# HDMI_RGB_LVDS_fertig_V3_nacked_keine_sti.net
KiCad netlist of a schematic drawn in EAGLE
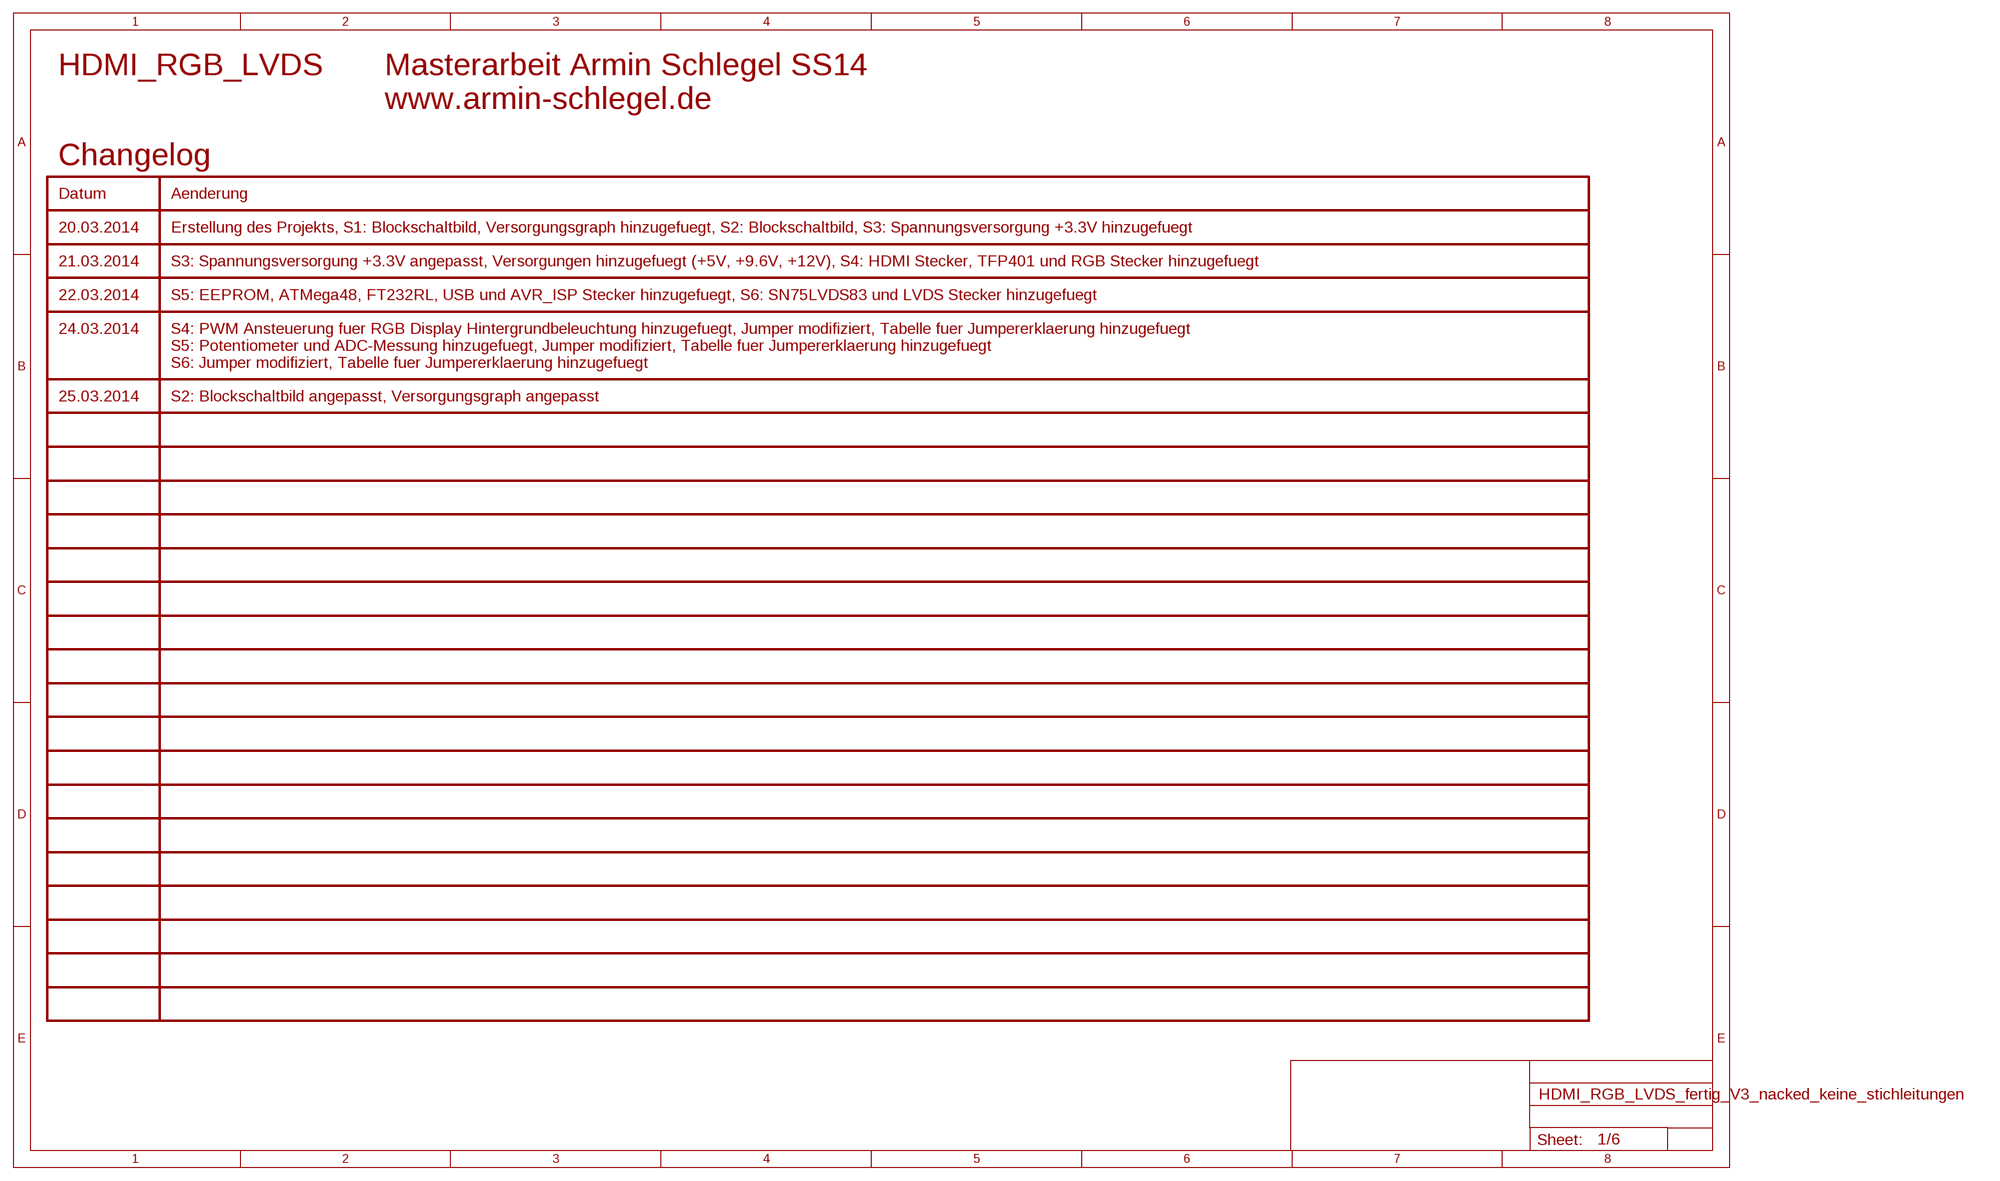
[diagram p0: schematic, sheet 1]
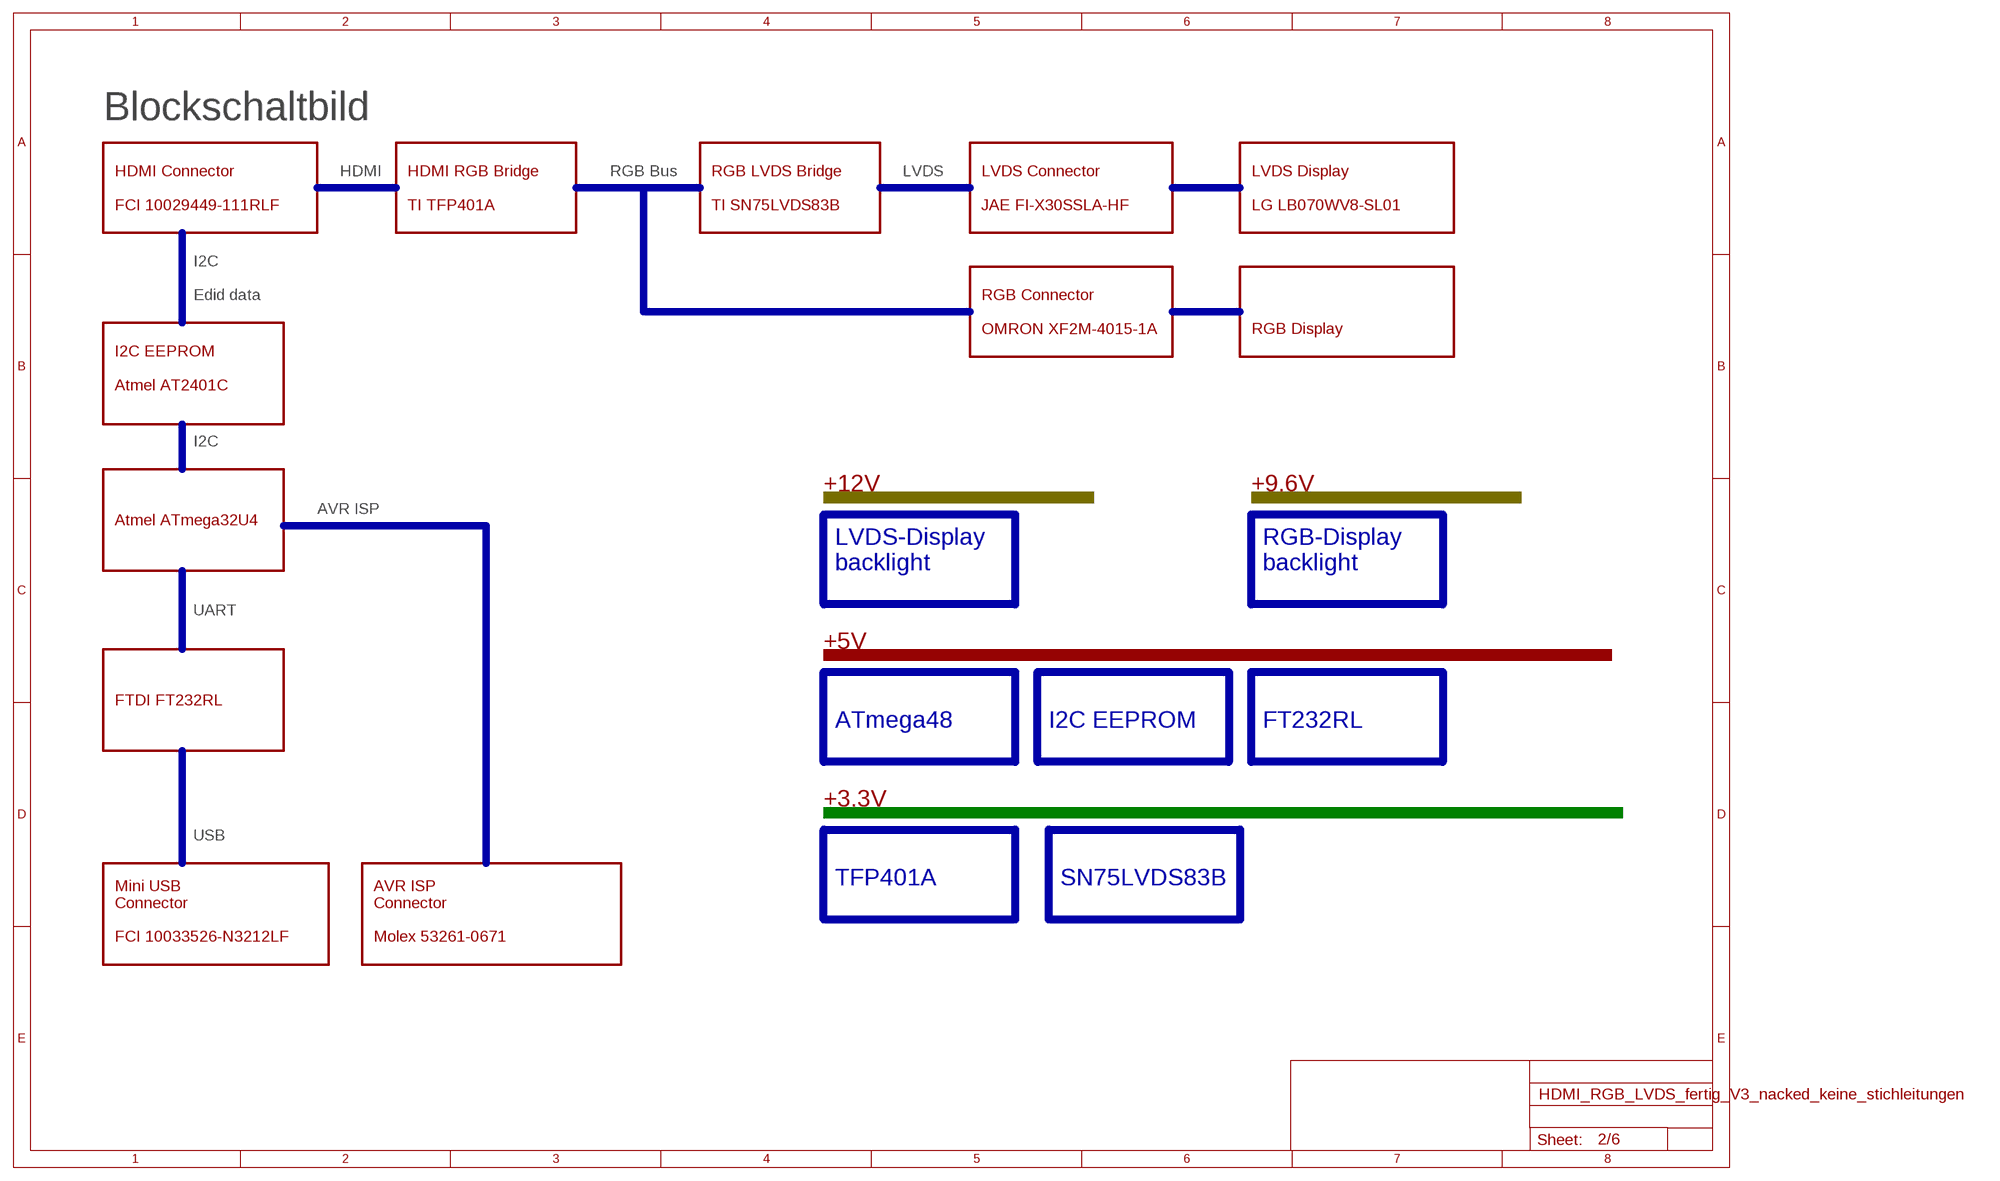
[diagram p1: schematic, sheet 2]
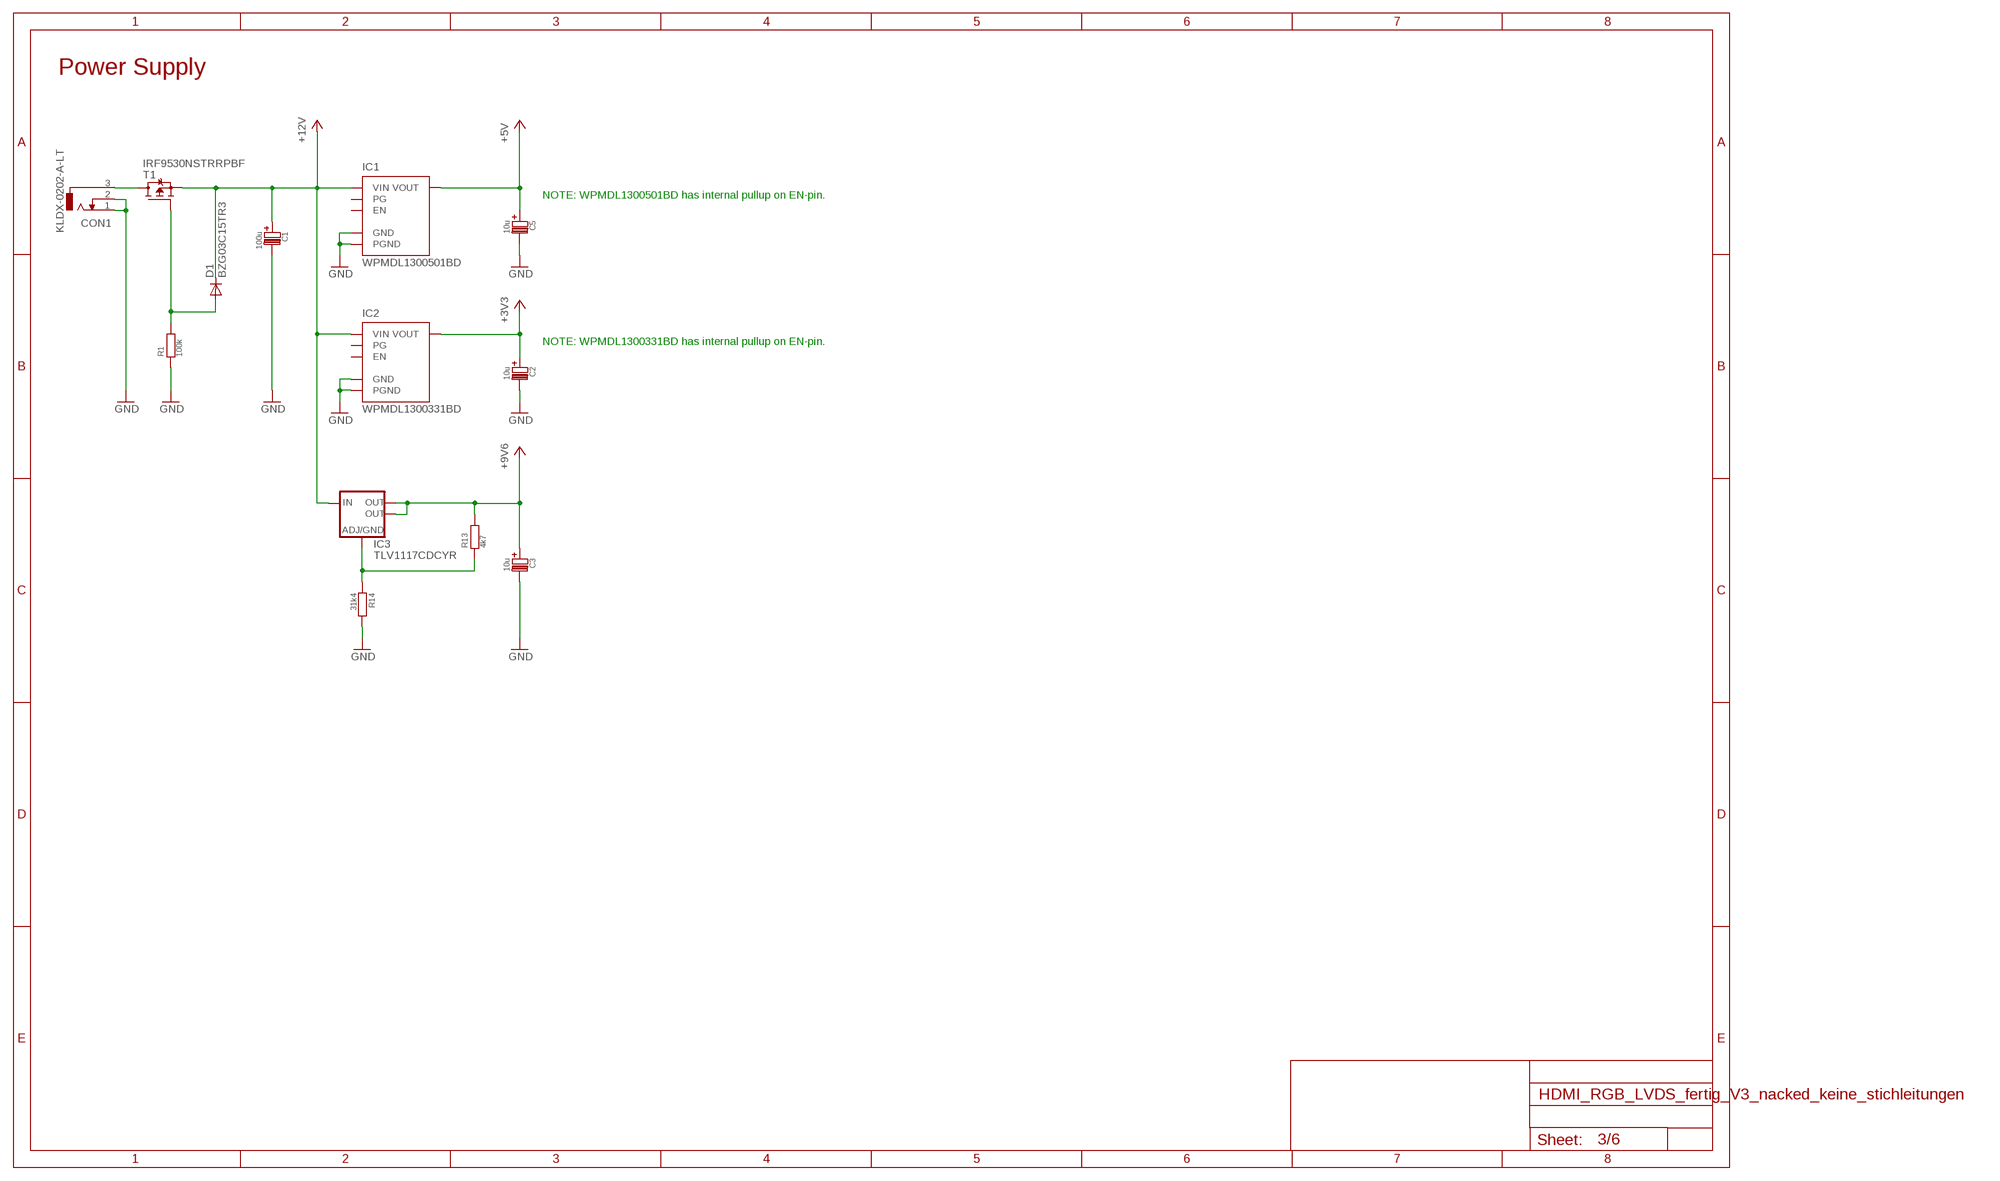
[diagram p2: schematic, sheet 3]
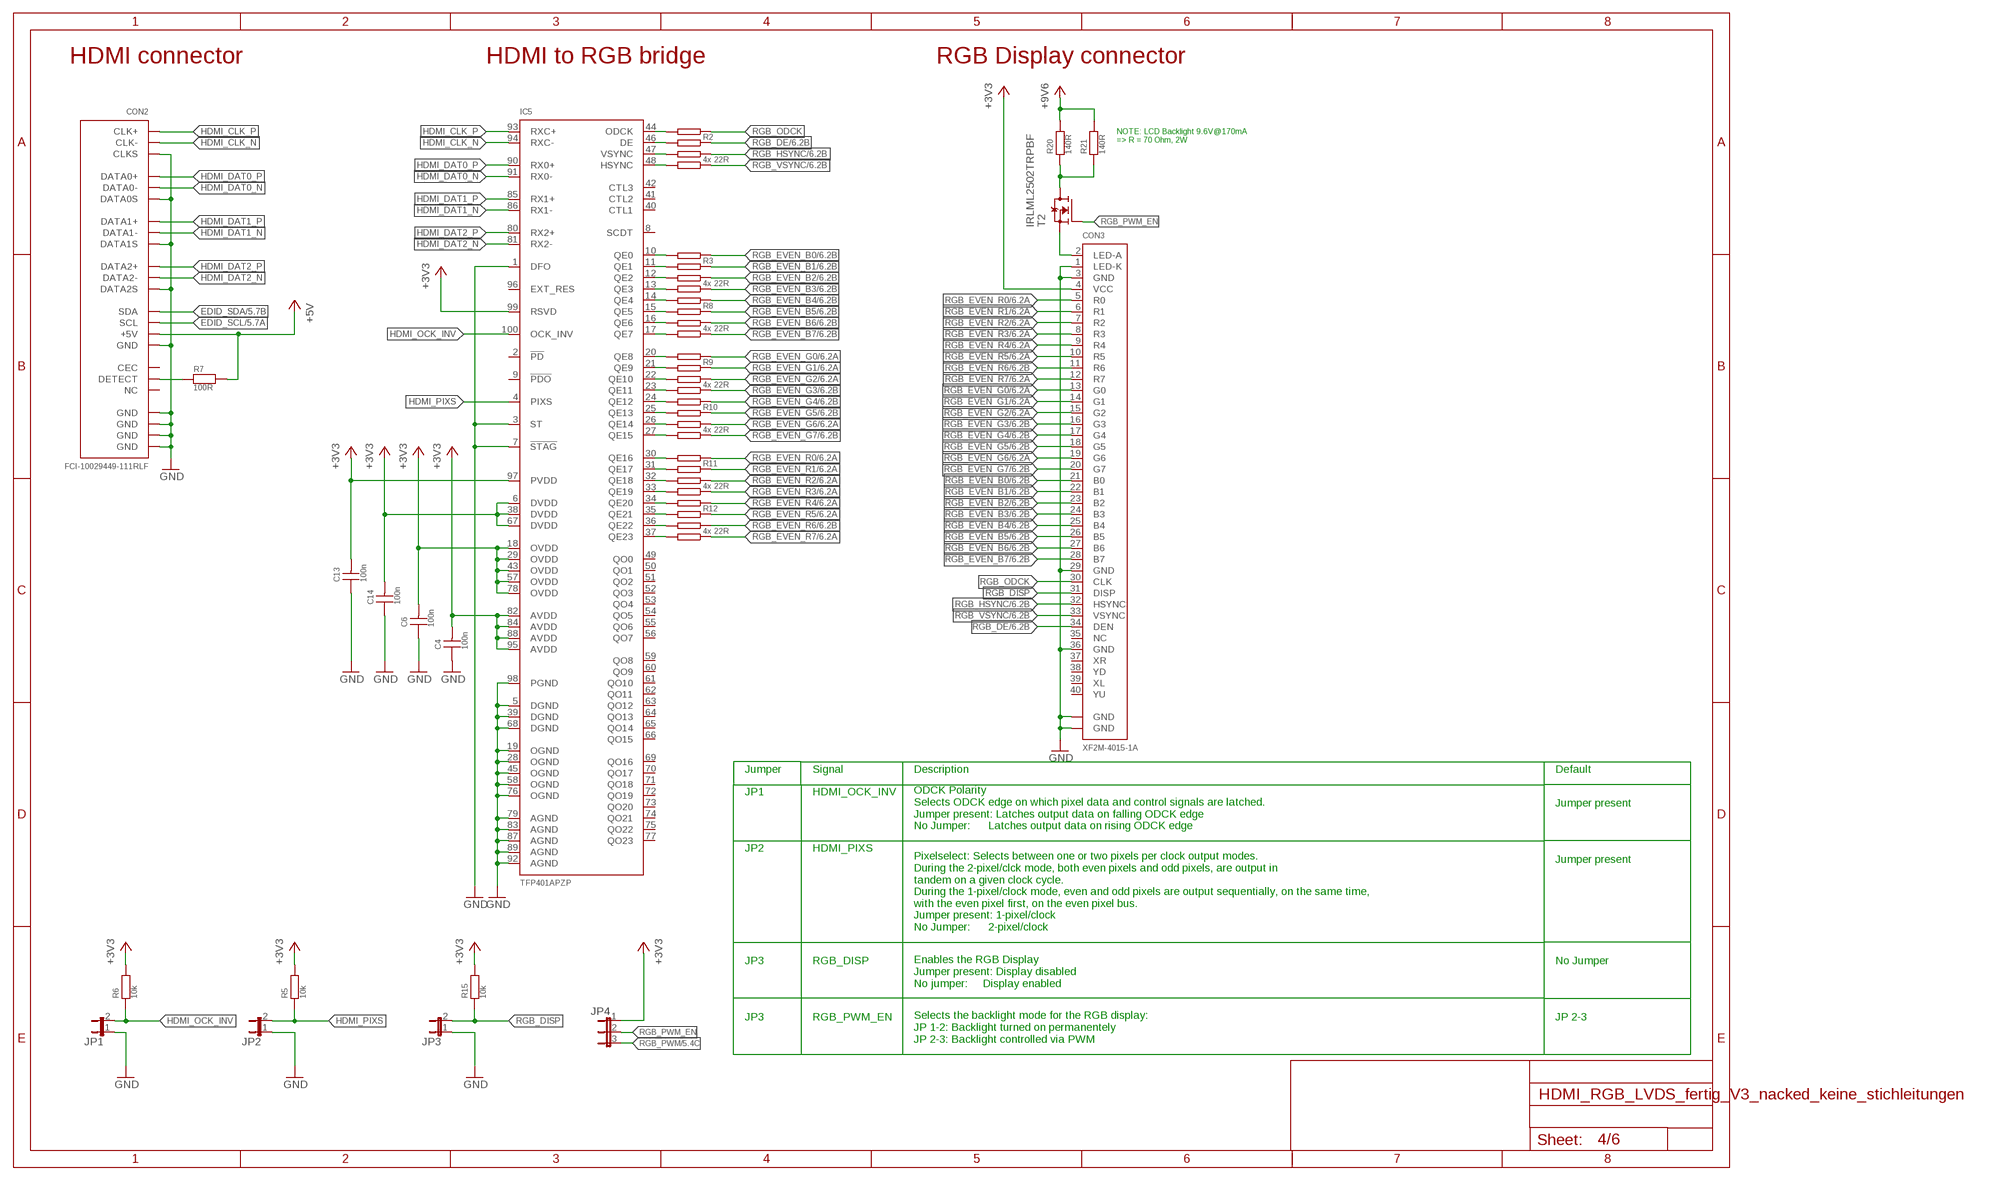
[diagram p3: schematic, sheet 4]
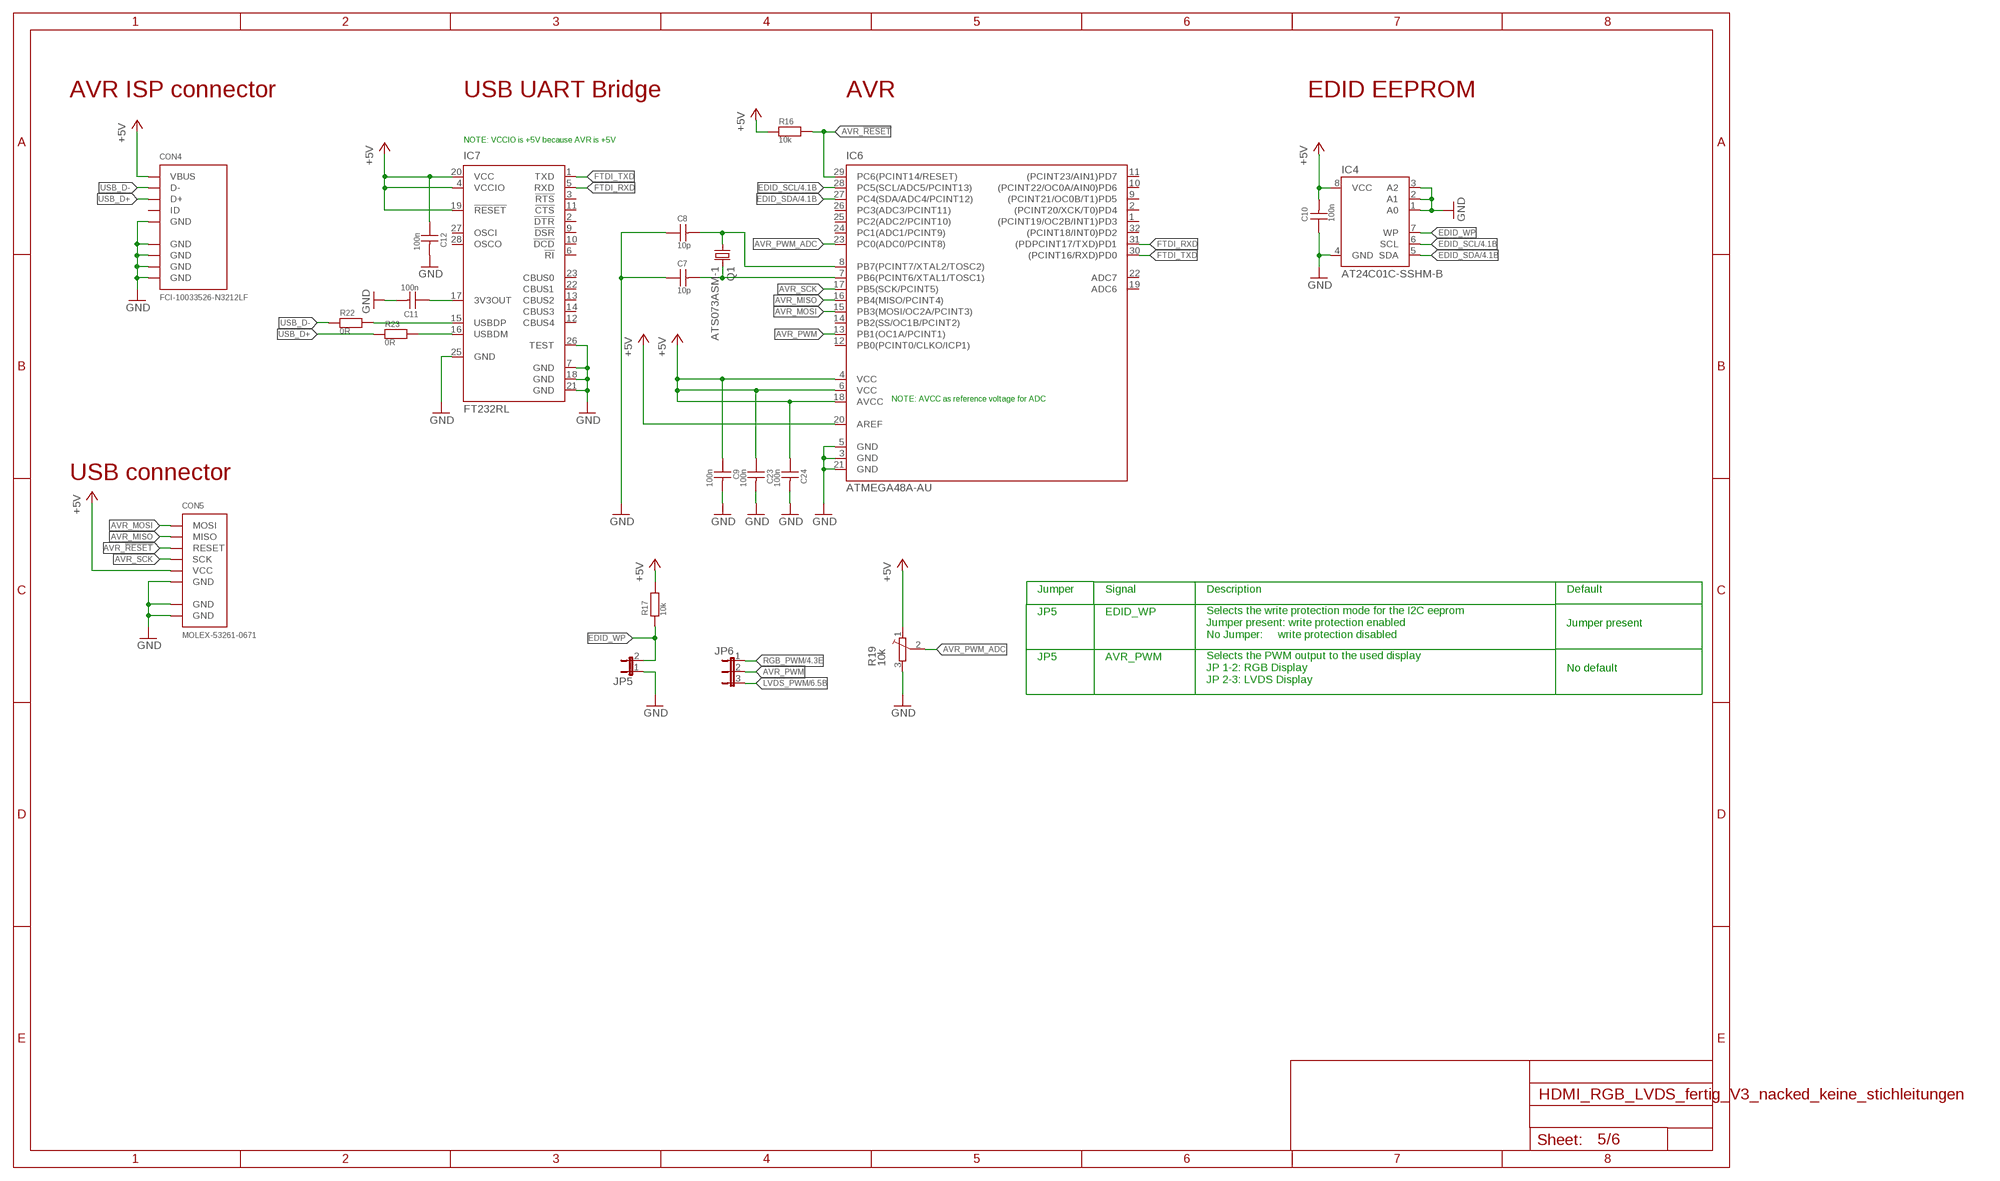
[diagram p4: schematic, sheet 5]
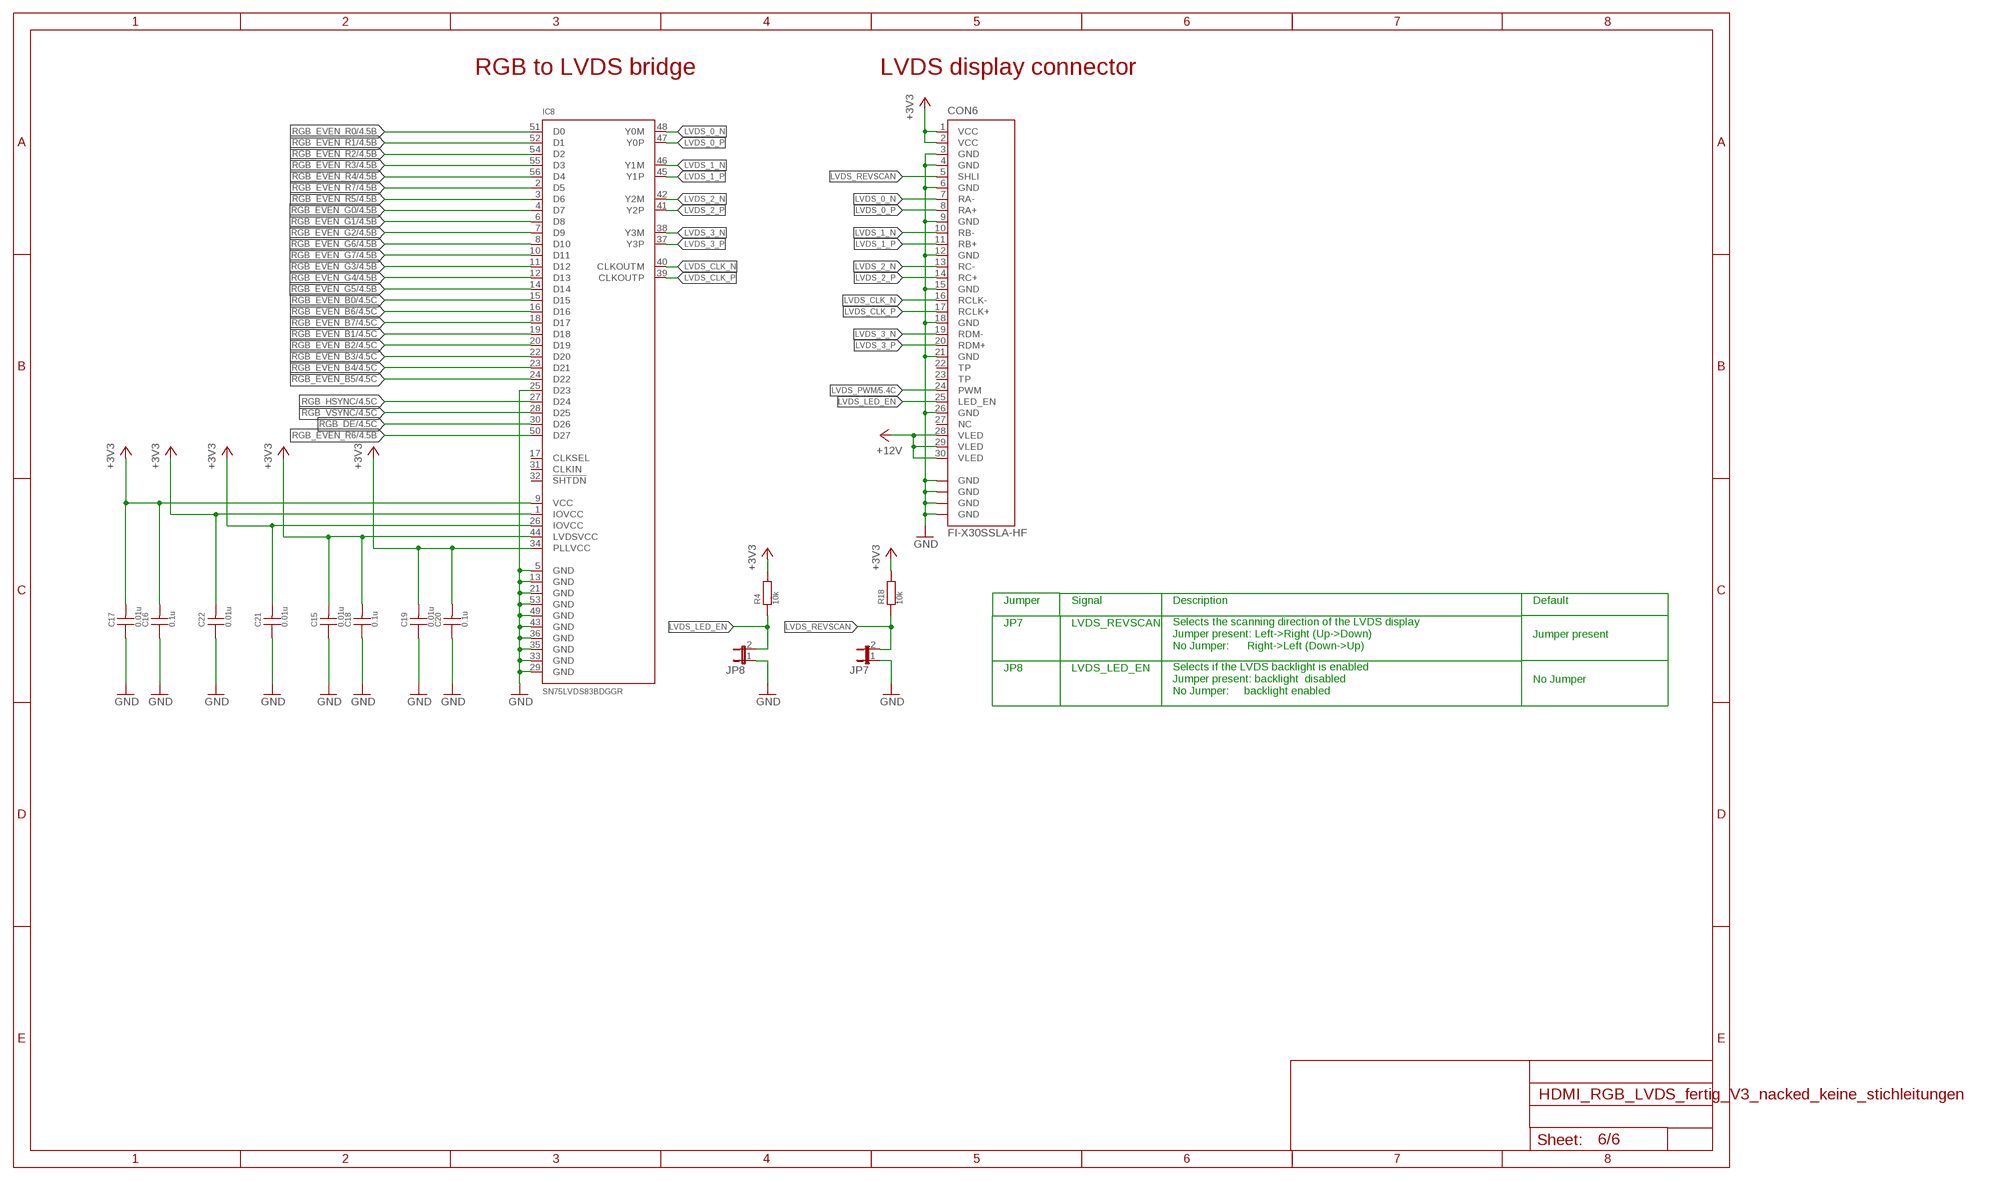
[diagram p5: schematic, sheet 6]

(export (version "E")
  (design (tool "Eeschema 10.0.6"))
  (components
    (comp (ref "C1")
      (value "100u")
      (footprint "eagle-import:C_POL_6X6MM")
      (libsource (lib "eagle-import") (part "C_POL6X6MM"))
    )
    (comp (ref "C2")
      (value "10u")
      (footprint "eagle-import:C_POL_4X4MM")
      (libsource (lib "eagle-import") (part "C_POL4X4MM"))
    )
    (comp (ref "C3")
      (value "10u")
      (footprint "eagle-import:C_POL_4X4MM")
      (libsource (lib "eagle-import") (part "C_POL4X4MM"))
    )
    (comp (ref "C5")
      (value "10u")
      (footprint "eagle-import:C_POL_4X4MM")
      (libsource (lib "eagle-import") (part "C_POL4X4MM"))
    )
    (comp (ref "CON1")
      (value "KLDX-0202-A-LT")
      (footprint "eagle-import:KLDX-0202-A-LT")
      (libsource (lib "eagle-import") (part "KLDX-0202-A-LT"))
    )
    (comp (ref "D1")
      (value "BZG03C15TR3")
      (footprint "eagle-import:DO214A")
      (libsource (lib "eagle-import") (part "BZG03C15TR3"))
    )
    (comp (ref "IC1")
      (value "WPMDL1300501BD")
      (footprint "eagle-import:TO263-5")
      (libsource (lib "eagle-import") (part "WPMDL1300501BD"))
    )
    (comp (ref "IC2")
      (value "WPMDL1300331BD")
      (footprint "eagle-import:TO263-5")
      (libsource (lib "eagle-import") (part "WPMDL1300331BD"))
    )
    (comp (ref "IC3")
      (value "TLV1117CDCYR")
      (footprint "eagle-import:SOT223")
      (libsource (lib "eagle-import") (part "TLV1117CDCYR"))
    )
    (comp (ref "R1")
      (value "100k")
      (footprint "eagle-import:R0402")
      (libsource (lib "eagle-import") (part "R0402"))
    )
    (comp (ref "R13")
      (value "4k7")
      (footprint "eagle-import:R0402")
      (libsource (lib "eagle-import") (part "R0402"))
    )
    (comp (ref "R14")
      (value "31k4")
      (footprint "eagle-import:R0402")
      (libsource (lib "eagle-import") (part "R0402"))
    )
    (comp (ref "T1")
      (value "IRF9530NSTRRPBF")
      (footprint "eagle-import:D2PAK")
      (libsource (lib "eagle-import") (part "IRF9530NSTRRPBF"))
    )
    (comp (ref "U$2")
      (value "FRAME_A3_LANDSCAPE")
      (footprint "eagle-import:FRAME")
      (libsource (lib "eagle-import") (part "FRAME_A3_LANDSCAPE"))
    )
    (comp (ref "U$1")
      (value "FRAME_A3_LANDSCAPE")
      (footprint "eagle-import:FRAME")
      (libsource (lib "eagle-import") (part "FRAME_A3_LANDSCAPE"))
    )
    (comp (ref "C4")
      (value "100n")
      (footprint "eagle-import:C0402")
      (libsource (lib "eagle-import") (part "C_SMD0402"))
    )
    (comp (ref "C6")
      (value "100n")
      (footprint "eagle-import:C0402")
      (libsource (lib "eagle-import") (part "C_SMD0402"))
    )
    (comp (ref "C13")
      (value "100n")
      (footprint "eagle-import:C0402")
      (libsource (lib "eagle-import") (part "C_SMD0402"))
    )
    (comp (ref "C14")
      (value "100n")
      (footprint "eagle-import:C0402")
      (libsource (lib "eagle-import") (part "C_SMD0402"))
    )
    (comp (ref "CON2")
      (value "FCI-10029449-111RLF")
      (footprint "eagle-import:FCI-10029449-111RLF")
      (libsource (lib "eagle-import") (part "FCI-10029449-111RLF"))
    )
    (comp (ref "CON3")
      (value "XF2M-4015-1A")
      (footprint "eagle-import:XF2M-4015-1A")
      (libsource (lib "eagle-import") (part "XF2M-4015-1A"))
    )
    (comp (ref "IC5")
      (value "TFP401APZP")
      (footprint "eagle-import:HTQFP-100")
      (libsource (lib "eagle-import") (part "TFP401APZP"))
    )
    (comp (ref "JP1")
      (value "JUMPER2")
      (footprint "eagle-import:JUMPER2_THROUGHHOLE")
      (libsource (lib "eagle-import") (part "JUMPER2"))
    )
    (comp (ref "JP2")
      (value "JUMPER2")
      (footprint "eagle-import:JUMPER2_THROUGHHOLE")
      (libsource (lib "eagle-import") (part "JUMPER2"))
    )
    (comp (ref "JP3")
      (value "JUMPER2")
      (footprint "eagle-import:JUMPER2_THROUGHHOLE")
      (libsource (lib "eagle-import") (part "JUMPER2"))
    )
    (comp (ref "JP4")
      (value "JUMPER3")
      (footprint "eagle-import:JUMPER3_THROUGHHOLE")
      (libsource (lib "eagle-import") (part "JUMPER3"))
    )
    (comp (ref "R2")
      (value "22R")
      (footprint "eagle-import:R-ARRAY-4X0603")
      (libsource (lib "eagle-import") (part "CTR-742C083220JP-4X22R-4X0603"))
    )
    (comp (ref "R3")
      (value "22R")
      (footprint "eagle-import:R-ARRAY-4X0603")
      (libsource (lib "eagle-import") (part "CTR-742C083220JP-4X22R-4X0603"))
    )
    (comp (ref "R5")
      (value "10k")
      (footprint "eagle-import:R0402")
      (libsource (lib "eagle-import") (part "R0402"))
    )
    (comp (ref "R6")
      (value "10k")
      (footprint "eagle-import:R0402")
      (libsource (lib "eagle-import") (part "R0402"))
    )
    (comp (ref "R7")
      (value "100R")
      (footprint "eagle-import:R0402")
      (libsource (lib "eagle-import") (part "R0402"))
    )
    (comp (ref "R8")
      (value "22R")
      (footprint "eagle-import:R-ARRAY-4X0603")
      (libsource (lib "eagle-import") (part "CTR-742C083220JP-4X22R-4X0603"))
    )
    (comp (ref "R9")
      (value "22R")
      (footprint "eagle-import:R-ARRAY-4X0603")
      (libsource (lib "eagle-import") (part "CTR-742C083220JP-4X22R-4X0603"))
    )
    (comp (ref "R10")
      (value "22R")
      (footprint "eagle-import:R-ARRAY-4X0603")
      (libsource (lib "eagle-import") (part "CTR-742C083220JP-4X22R-4X0603"))
    )
    (comp (ref "R11")
      (value "22R")
      (footprint "eagle-import:R-ARRAY-4X0603")
      (libsource (lib "eagle-import") (part "CTR-742C083220JP-4X22R-4X0603"))
    )
    (comp (ref "R12")
      (value "22R")
      (footprint "eagle-import:R-ARRAY-4X0603")
      (libsource (lib "eagle-import") (part "CTR-742C083220JP-4X22R-4X0603"))
    )
    (comp (ref "R15")
      (value "10k")
      (footprint "eagle-import:R0402")
      (libsource (lib "eagle-import") (part "R0402"))
    )
    (comp (ref "R20")
      (value "140R")
      (footprint "eagle-import:R2512")
      (libsource (lib "eagle-import") (part "R2512"))
    )
    (comp (ref "R21")
      (value "140R")
      (footprint "eagle-import:R2512")
      (libsource (lib "eagle-import") (part "R2512"))
    )
    (comp (ref "T2")
      (value "IRLML2502TRPBF")
      (footprint "eagle-import:SOT23")
      (libsource (lib "eagle-import") (part "IRLML2502TRPBF"))
    )
    (comp (ref "U$3")
      (value "FRAME_A3_LANDSCAPE")
      (footprint "eagle-import:FRAME")
      (libsource (lib "eagle-import") (part "FRAME_A3_LANDSCAPE"))
    )
    (comp (ref "C7")
      (value "10p")
      (footprint "eagle-import:C0402")
      (libsource (lib "eagle-import") (part "C_SMD0402"))
    )
    (comp (ref "C8")
      (value "10p")
      (footprint "eagle-import:C0402")
      (libsource (lib "eagle-import") (part "C_SMD0402"))
    )
    (comp (ref "C9")
      (value "100n")
      (footprint "eagle-import:C0402")
      (libsource (lib "eagle-import") (part "C_SMD0402"))
    )
    (comp (ref "C10")
      (value "100n")
      (footprint "eagle-import:C0402")
      (libsource (lib "eagle-import") (part "C_SMD0402"))
    )
    (comp (ref "C11")
      (value "100n")
      (footprint "eagle-import:C0402")
      (libsource (lib "eagle-import") (part "C_SMD0402"))
    )
    (comp (ref "C12")
      (value "100n")
      (footprint "eagle-import:C0402")
      (libsource (lib "eagle-import") (part "C_SMD0402"))
    )
    (comp (ref "C23")
      (value "100n")
      (footprint "eagle-import:C0402")
      (libsource (lib "eagle-import") (part "C_SMD0402"))
    )
    (comp (ref "C24")
      (value "100n")
      (footprint "eagle-import:C0402")
      (libsource (lib "eagle-import") (part "C_SMD0402"))
    )
    (comp (ref "CON4")
      (value "FCI-10033526-N3212LF")
      (footprint "eagle-import:FCI-10033526-N3212LF")
      (libsource (lib "eagle-import") (part "FCI-10033526-N3212LF"))
    )
    (comp (ref "CON5")
      (value "MOLEX-53261-0671")
      (footprint "eagle-import:MOLEX-53261-0671")
      (libsource (lib "eagle-import") (part "MOLEX-53261-0671"))
    )
    (comp (ref "IC4")
      (value "AT24C01C-SSHM-B")
      (footprint "eagle-import:SOIC8")
      (libsource (lib "eagle-import") (part "AT24C01C-SSHM-B"))
    )
    (comp (ref "IC6")
      (value "ATMEGA48A-AU")
      (footprint "eagle-import:TQFP32")
      (libsource (lib "eagle-import") (part "ATMEGA48A-AU"))
    )
    (comp (ref "IC7")
      (value "FT232RL")
      (footprint "eagle-import:SSOP28")
      (libsource (lib "eagle-import") (part "FT232RL"))
    )
    (comp (ref "JP5")
      (value "JUMPER2")
      (footprint "eagle-import:JUMPER2_THROUGHHOLE")
      (libsource (lib "eagle-import") (part "JUMPER2"))
    )
    (comp (ref "JP6")
      (value "JUMPER3")
      (footprint "eagle-import:JUMPER3_THROUGHHOLE")
      (libsource (lib "eagle-import") (part "JUMPER3"))
    )
    (comp (ref "Q1")
      (value "ATS073ASM-1")
      (footprint "eagle-import:HC49_USSM")
      (libsource (lib "eagle-import") (part "ATS073ASM-1"))
    )
    (comp (ref "R16")
      (value "10k")
      (footprint "eagle-import:R0402")
      (libsource (lib "eagle-import") (part "R0402"))
    )
    (comp (ref "R17")
      (value "10k")
      (footprint "eagle-import:R0402")
      (libsource (lib "eagle-import") (part "R0402"))
    )
    (comp (ref "R19")
      (value "10k")
      (footprint "eagle-import:35WR5KLFTR")
      (libsource (lib "eagle-import") (part "35WR5KLFTR"))
    )
    (comp (ref "R22")
      (value "0R")
      (footprint "eagle-import:R0402")
      (libsource (lib "eagle-import") (part "R0402"))
    )
    (comp (ref "R23")
      (value "0R")
      (footprint "eagle-import:R0402")
      (libsource (lib "eagle-import") (part "R0402"))
    )
    (comp (ref "U$4")
      (value "FRAME_A3_LANDSCAPE")
      (footprint "eagle-import:FRAME")
      (libsource (lib "eagle-import") (part "FRAME_A3_LANDSCAPE"))
    )
    (comp (ref "C15")
      (value "0.01u")
      (footprint "eagle-import:C0402")
      (libsource (lib "eagle-import") (part "C_SMD0402"))
    )
    (comp (ref "C16")
      (value "0.1u")
      (footprint "eagle-import:C0402")
      (libsource (lib "eagle-import") (part "C_SMD0402"))
    )
    (comp (ref "C17")
      (value "0.01u")
      (footprint "eagle-import:C0402")
      (libsource (lib "eagle-import") (part "C_SMD0402"))
    )
    (comp (ref "C18")
      (value "0.1u")
      (footprint "eagle-import:C0402")
      (libsource (lib "eagle-import") (part "C_SMD0402"))
    )
    (comp (ref "C19")
      (value "0.01u")
      (footprint "eagle-import:C0402")
      (libsource (lib "eagle-import") (part "C_SMD0402"))
    )
    (comp (ref "C20")
      (value "0.1u")
      (footprint "eagle-import:C0402")
      (libsource (lib "eagle-import") (part "C_SMD0402"))
    )
    (comp (ref "C21")
      (value "0.01u")
      (footprint "eagle-import:C0402")
      (libsource (lib "eagle-import") (part "C_SMD0402"))
    )
    (comp (ref "C22")
      (value "0.01u")
      (footprint "eagle-import:C0402")
      (libsource (lib "eagle-import") (part "C_SMD0402"))
    )
    (comp (ref "CON6")
      (value "FI-X30SSLA-HF")
      (footprint "eagle-import:FI-X30SSLA-HF")
      (libsource (lib "eagle-import") (part "FI-X30SSLA-HF"))
    )
    (comp (ref "IC8")
      (value "SN75LVDS83BDGGR")
      (footprint "eagle-import:TSSOP-56")
      (libsource (lib "eagle-import") (part "SN75LVDS83BDGGR"))
    )
    (comp (ref "JP7")
      (value "JUMPER2")
      (footprint "eagle-import:JUMPER2_THROUGHHOLE")
      (libsource (lib "eagle-import") (part "JUMPER2"))
    )
    (comp (ref "JP8")
      (value "JUMPER2")
      (footprint "eagle-import:JUMPER2_THROUGHHOLE")
      (libsource (lib "eagle-import") (part "JUMPER2"))
    )
    (comp (ref "R4")
      (value "10k")
      (footprint "eagle-import:R0402")
      (libsource (lib "eagle-import") (part "R0402"))
    )
    (comp (ref "R18")
      (value "10k")
      (footprint "eagle-import:R0402")
      (libsource (lib "eagle-import") (part "R0402"))
    )
    (comp (ref "U$5")
      (value "FRAME_A3_LANDSCAPE")
      (footprint "eagle-import:FRAME")
      (libsource (lib "eagle-import") (part "FRAME_A3_LANDSCAPE"))
    )
    (comp (ref "U$15")
      (value "FRAME_A3_LANDSCAPE")
      (footprint "eagle-import:FRAME")
      (libsource (lib "eagle-import") (part "FRAME_A3_LANDSCAPE"))
    )
  )
  (nets
    (net (code "3") (name "+3V3") (class "Default")
      (node (ref "C13") (pin "2") (pinfunction "P$2_2") (pintype "passive"))
      (node (ref "C14") (pin "2") (pinfunction "P$2_2") (pintype "passive"))
      (node (ref "C15") (pin "2") (pinfunction "P$2_2") (pintype "passive"))
      (node (ref "C16") (pin "2") (pinfunction "P$2_2") (pintype "passive"))
      (node (ref "C17") (pin "2") (pinfunction "P$2_2") (pintype "passive"))
      (node (ref "C18") (pin "2") (pinfunction "P$2_2") (pintype "passive"))
      (node (ref "C19") (pin "2") (pinfunction "P$2_2") (pintype "passive"))
      (node (ref "C2") (pin "+") (pinfunction "P$1_+") (pintype "passive"))
      (node (ref "C20") (pin "2") (pinfunction "P$2_2") (pintype "passive"))
      (node (ref "C21") (pin "2") (pinfunction "P$2_2") (pintype "passive"))
      (node (ref "C22") (pin "2") (pinfunction "P$2_2") (pintype "passive"))
      (node (ref "C4") (pin "2") (pinfunction "P$2_2") (pintype "passive"))
      (node (ref "C6") (pin "2") (pinfunction "P$2_2") (pintype "passive"))
      (node (ref "CON3") (pin "4") (pinfunction "VCC_4") (pintype "bidirectional"))
      (node (ref "CON6") (pin "1") (pinfunction "VCC_1") (pintype "bidirectional"))
      (node (ref "CON6") (pin "2") (pinfunction "VCC_2") (pintype "bidirectional"))
      (node (ref "IC2") (pin "3") (pinfunction "VOUT_3") (pintype "bidirectional"))
      (node (ref "IC5") (pin "18") (pinfunction "OVDD_18") (pintype "power_in"))
      (node (ref "IC5") (pin "29") (pinfunction "OVDD_29") (pintype "power_in"))
      (node (ref "IC5") (pin "38") (pinfunction "DVDD_38") (pintype "power_in"))
      (node (ref "IC5") (pin "43") (pinfunction "OVDD_43") (pintype "power_in"))
      (node (ref "IC5") (pin "57") (pinfunction "OVDD_57") (pintype "power_in"))
      (node (ref "IC5") (pin "6") (pinfunction "DVDD_6") (pintype "power_in"))
      (node (ref "IC5") (pin "67") (pinfunction "DVDD_67") (pintype "power_in"))
      (node (ref "IC5") (pin "78") (pinfunction "OVDD_78") (pintype "power_in"))
      (node (ref "IC5") (pin "82") (pinfunction "AVDD_82") (pintype "power_in"))
      (node (ref "IC5") (pin "84") (pinfunction "AVDD_84") (pintype "power_in"))
      (node (ref "IC5") (pin "88") (pinfunction "AVDD_88") (pintype "power_in"))
      (node (ref "IC5") (pin "95") (pinfunction "AVDD_95") (pintype "power_in"))
      (node (ref "IC5") (pin "97") (pinfunction "PVDD_97") (pintype "power_in"))
      (node (ref "IC5") (pin "99") (pinfunction "RSVD_99") (pintype "bidirectional"))
      (node (ref "IC8") (pin "1") (pinfunction "IOVCC_1") (pintype "power_in"))
      (node (ref "IC8") (pin "26") (pinfunction "IOVCC_26") (pintype "power_in"))
      (node (ref "IC8") (pin "34") (pinfunction "PLLVCC_34") (pintype "power_in"))
      (node (ref "IC8") (pin "44") (pinfunction "LVDSVCC_44") (pintype "power_in"))
      (node (ref "IC8") (pin "9") (pinfunction "VCC_9") (pintype "power_in"))
      (node (ref "JP4") (pin "1") (pinfunction "1_1") (pintype "passive"))
      (node (ref "R15") (pin "2") (pinfunction "P$2_2") (pintype "passive"))
      (node (ref "R18") (pin "2") (pinfunction "P$2_2") (pintype "passive"))
      (node (ref "R4") (pin "2") (pinfunction "P$2_2") (pintype "passive"))
      (node (ref "R5") (pin "2") (pinfunction "P$2_2") (pintype "passive"))
      (node (ref "R6") (pin "2") (pinfunction "P$2_2") (pintype "passive"))
    )
    (net (code "4") (name "+5V") (class "Default")
      (node (ref "C10") (pin "2") (pinfunction "P$2_2") (pintype "passive"))
      (node (ref "C12") (pin "1") (pinfunction "P$1_1") (pintype "passive"))
      (node (ref "C23") (pin "1") (pinfunction "P$1_1") (pintype "passive"))
      (node (ref "C24") (pin "1") (pinfunction "P$1_1") (pintype "passive"))
      (node (ref "C5") (pin "+") (pinfunction "P$1_+") (pintype "passive"))
      (node (ref "C9") (pin "1") (pinfunction "P$1_1") (pintype "passive"))
      (node (ref "CON2") (pin "18") (pinfunction "+5V_18") (pintype "bidirectional"))
      (node (ref "CON4") (pin "1") (pinfunction "VBUS_1") (pintype "bidirectional"))
      (node (ref "CON5") (pin "5") (pinfunction "VCC_5") (pintype "bidirectional"))
      (node (ref "IC1") (pin "3") (pinfunction "VOUT_3") (pintype "bidirectional"))
      (node (ref "IC4") (pin "8") (pinfunction "VCC_8") (pintype "power_in"))
      (node (ref "IC6") (pin "18") (pinfunction "AVCC_18") (pintype "power_in"))
      (node (ref "IC6") (pin "20") (pinfunction "AREF_20") (pintype "power_in"))
      (node (ref "IC6") (pin "4") (pinfunction "VCC_4") (pintype "power_in"))
      (node (ref "IC6") (pin "6") (pinfunction "VCC_6") (pintype "power_in"))
      (node (ref "IC7") (pin "19") (pinfunction "~{RESET}_19") (pintype "input"))
      (node (ref "IC7") (pin "20") (pinfunction "VCC_20") (pintype "power_in"))
      (node (ref "IC7") (pin "4") (pinfunction "VCCIO_4") (pintype "power_in"))
      (node (ref "R16") (pin "1") (pinfunction "P$1_1") (pintype "passive"))
      (node (ref "R17") (pin "2") (pinfunction "P$2_2") (pintype "passive"))
      (node (ref "R19") (pin "1") (pinfunction "E_1") (pintype "passive"))
      (node (ref "R7") (pin "2") (pinfunction "P$2_2") (pintype "passive"))
    )
    (net (code "5") (name "+9V6") (class "Default")
      (node (ref "C3") (pin "+") (pinfunction "P$1_+") (pintype "passive"))
      (node (ref "IC3") (pin "2") (pinfunction "OUT_2") (pintype "passive"))
      (node (ref "IC3") (pin "4") (pinfunction "OUT1_4") (pintype "passive"))
      (node (ref "R13") (pin "2") (pinfunction "P$2_2") (pintype "passive"))
      (node (ref "R20") (pin "2") (pinfunction "P$2_2") (pintype "passive"))
      (node (ref "R21") (pin "2") (pinfunction "P$2_2") (pintype "passive"))
    )
    (net (code "6") (name "+12V") (class "Default")
      (node (ref "C1") (pin "+") (pinfunction "P$1_+") (pintype "passive"))
      (node (ref "CON6") (pin "28") (pinfunction "VLED_28") (pintype "bidirectional"))
      (node (ref "CON6") (pin "29") (pinfunction "VLED_29") (pintype "bidirectional"))
      (node (ref "CON6") (pin "30") (pinfunction "VLED_30") (pintype "bidirectional"))
      (node (ref "D1") (pin "C") (pinfunction "C_C") (pintype "passive"))
      (node (ref "IC1") (pin "1") (pinfunction "VIN_1") (pintype "bidirectional"))
      (node (ref "IC2") (pin "1") (pinfunction "VIN_1") (pintype "bidirectional"))
      (node (ref "IC3") (pin "3") (pinfunction "IN_3") (pintype "input"))
      (node (ref "T1") (pin "3") (pinfunction "S_3") (pintype "passive"))
    )
    (net (code "9") (name "AVR_MISO") (class "Default")
      (node (ref "CON5") (pin "2") (pinfunction "MISO_2") (pintype "bidirectional"))
      (node (ref "IC6") (pin "16") (pinfunction "PB4(MISO/PCINT4)_16") (pintype "bidirectional"))
    )
    (net (code "10") (name "AVR_MOSI") (class "Default")
      (node (ref "CON5") (pin "1") (pinfunction "MOSI_1") (pintype "bidirectional"))
      (node (ref "IC6") (pin "15") (pinfunction "PB3(MOSI/OC2A/PCINT3)_15") (pintype "bidirectional"))
    )
    (net (code "11") (name "AVR_PWM") (class "Default")
      (node (ref "IC6") (pin "13") (pinfunction "PB1(OC1A/PCINT1)_13") (pintype "bidirectional"))
      (node (ref "JP6") (pin "2") (pinfunction "2_2") (pintype "passive"))
    )
    (net (code "12") (name "AVR_PWM_ADC") (class "Default")
      (node (ref "IC6") (pin "23") (pinfunction "PC0(ADC0/PCINT8)_23") (pintype "bidirectional"))
      (node (ref "R19") (pin "2") (pinfunction "S_2") (pintype "passive"))
    )
    (net (code "13") (name "AVR_SCK") (class "Default")
      (node (ref "CON5") (pin "4") (pinfunction "SCK_4") (pintype "bidirectional"))
      (node (ref "IC6") (pin "17") (pinfunction "PB5(SCK/PCINT5)_17") (pintype "bidirectional"))
    )
    (net (code "14") (name "AVR_~{RESET}") (class "Default")
      (node (ref "CON5") (pin "3") (pinfunction "RESET_3") (pintype "bidirectional"))
      (node (ref "IC6") (pin "29") (pinfunction "PC6(PCINT14/RESET)_29") (pintype "bidirectional"))
      (node (ref "R16") (pin "2") (pinfunction "P$2_2") (pintype "passive"))
    )
    (net (code "15") (name "EDID_SCL") (class "Default")
      (node (ref "CON2") (pin "15") (pinfunction "SCL_15") (pintype "bidirectional"))
      (node (ref "IC4") (pin "6") (pinfunction "SCL_6") (pintype "bidirectional"))
      (node (ref "IC6") (pin "28") (pinfunction "PC5(SCL/ADC5/PCINT13)_28") (pintype "bidirectional"))
    )
    (net (code "16") (name "EDID_SDA") (class "Default")
      (node (ref "CON2") (pin "16") (pinfunction "SDA_16") (pintype "bidirectional"))
      (node (ref "IC4") (pin "5") (pinfunction "SDA_5") (pintype "bidirectional"))
      (node (ref "IC6") (pin "27") (pinfunction "PC4(SDA/ADC4/PCINT12)_27") (pintype "bidirectional"))
    )
    (net (code "17") (name "EDID_WP") (class "Default")
      (node (ref "IC4") (pin "7") (pinfunction "WP_7") (pintype "input"))
      (node (ref "JP5") (pin "2") (pinfunction "2_2") (pintype "passive"))
      (node (ref "R17") (pin "1") (pinfunction "P$1_1") (pintype "passive"))
    )
    (net (code "18") (name "FTDI_RXD") (class "Default")
      (node (ref "IC6") (pin "31") (pinfunction "(PDPCINT17/TXD)PD1_31") (pintype "bidirectional"))
      (node (ref "IC7") (pin "5") (pinfunction "RXD_5") (pintype "input"))
    )
    (net (code "19") (name "FTDI_TXD") (class "Default")
      (node (ref "IC6") (pin "30") (pinfunction "(PCINT16/RXD)PD0_30") (pintype "bidirectional"))
      (node (ref "IC7") (pin "1") (pinfunction "TXD_1") (pintype "output"))
    )
    (net (code "20") (name "GND") (class "Default")
      (node (ref "C1") (pin "-") (pinfunction "P$2_-") (pintype "passive"))
      (node (ref "C10") (pin "1") (pinfunction "P$1_1") (pintype "passive"))
      (node (ref "C11") (pin "2") (pinfunction "P$2_2") (pintype "passive"))
      (node (ref "C12") (pin "2") (pinfunction "P$2_2") (pintype "passive"))
      (node (ref "C13") (pin "1") (pinfunction "P$1_1") (pintype "passive"))
      (node (ref "C14") (pin "1") (pinfunction "P$1_1") (pintype "passive"))
      (node (ref "C15") (pin "1") (pinfunction "P$1_1") (pintype "passive"))
      (node (ref "C16") (pin "1") (pinfunction "P$1_1") (pintype "passive"))
      (node (ref "C17") (pin "1") (pinfunction "P$1_1") (pintype "passive"))
      (node (ref "C18") (pin "1") (pinfunction "P$1_1") (pintype "passive"))
      (node (ref "C19") (pin "1") (pinfunction "P$1_1") (pintype "passive"))
      (node (ref "C2") (pin "-") (pinfunction "P$2_-") (pintype "passive"))
      (node (ref "C20") (pin "1") (pinfunction "P$1_1") (pintype "passive"))
      (node (ref "C21") (pin "1") (pinfunction "P$1_1") (pintype "passive"))
      (node (ref "C22") (pin "1") (pinfunction "P$1_1") (pintype "passive"))
      (node (ref "C23") (pin "2") (pinfunction "P$2_2") (pintype "passive"))
      (node (ref "C24") (pin "2") (pinfunction "P$2_2") (pintype "passive"))
      (node (ref "C3") (pin "-") (pinfunction "P$2_-") (pintype "passive"))
      (node (ref "C4") (pin "1") (pinfunction "P$1_1") (pintype "passive"))
      (node (ref "C5") (pin "-") (pinfunction "P$2_-") (pintype "passive"))
      (node (ref "C6") (pin "1") (pinfunction "P$1_1") (pintype "passive"))
      (node (ref "C7") (pin "1") (pinfunction "P$1_1") (pintype "passive"))
      (node (ref "C8") (pin "1") (pinfunction "P$1_1") (pintype "passive"))
      (node (ref "C9") (pin "2") (pinfunction "P$2_2") (pintype "passive"))
      (node (ref "CON1") (pin "1") (pinfunction "3_1") (pintype "passive"))
      (node (ref "CON1") (pin "2") (pinfunction "2_2") (pintype "passive"))
      (node (ref "CON2") (pin "11") (pinfunction "CLKS_11") (pintype "bidirectional"))
      (node (ref "CON2") (pin "17") (pinfunction "GND_17") (pintype "bidirectional"))
      (node (ref "CON2") (pin "2") (pinfunction "DATA2S_2") (pintype "bidirectional"))
      (node (ref "CON2") (pin "5") (pinfunction "DATA1S_5") (pintype "bidirectional"))
      (node (ref "CON2") (pin "8") (pinfunction "DATA0S_8") (pintype "bidirectional"))
      (node (ref "CON2") (pin "GND@1") (pinfunction "GND_GND@1") (pintype "power_in"))
      (node (ref "CON2") (pin "GND@2") (pinfunction "GND_GND@2") (pintype "power_in"))
      (node (ref "CON2") (pin "GND@3") (pinfunction "GND_GND@3") (pintype "power_in"))
      (node (ref "CON2") (pin "GND@4") (pinfunction "GND_GND@4") (pintype "power_in"))
      (node (ref "CON3") (pin "1") (pinfunction "LED-K_1") (pintype "bidirectional"))
      (node (ref "CON3") (pin "29") (pinfunction "GND_29") (pintype "bidirectional"))
      (node (ref "CON3") (pin "3") (pinfunction "GND_3") (pintype "bidirectional"))
      (node (ref "CON3") (pin "36") (pinfunction "GND_36") (pintype "bidirectional"))
      (node (ref "CON3") (pin "GND@1") (pinfunction "GND_GND@1") (pintype "power_in"))
      (node (ref "CON3") (pin "GND@2") (pinfunction "GND_GND@2") (pintype "power_in"))
      (node (ref "CON4") (pin "5") (pinfunction "GND_5") (pintype "bidirectional"))
      (node (ref "CON4") (pin "GND@1") (pinfunction "GND_GND@1") (pintype "power_in"))
      (node (ref "CON4") (pin "GND@2") (pinfunction "GND_GND@2") (pintype "power_in"))
      (node (ref "CON4") (pin "GND@3") (pinfunction "GND_GND@3") (pintype "power_in"))
      (node (ref "CON4") (pin "GND@4") (pinfunction "GND_GND@4") (pintype "power_in"))
      (node (ref "CON5") (pin "6") (pinfunction "GND_6") (pintype "bidirectional"))
      (node (ref "CON5") (pin "GND@1") (pinfunction "GND_GND@1") (pintype "power_in"))
      (node (ref "CON5") (pin "GND@2") (pinfunction "GND_GND@2") (pintype "power_in"))
      (node (ref "CON6") (pin "12") (pinfunction "GND_12") (pintype "bidirectional"))
      (node (ref "CON6") (pin "15") (pinfunction "GND_15") (pintype "bidirectional"))
      (node (ref "CON6") (pin "18") (pinfunction "GND_18") (pintype "bidirectional"))
      (node (ref "CON6") (pin "21") (pinfunction "GND_21") (pintype "bidirectional"))
      (node (ref "CON6") (pin "26") (pinfunction "GND_26") (pintype "bidirectional"))
      (node (ref "CON6") (pin "3") (pinfunction "GND_3") (pintype "bidirectional"))
      (node (ref "CON6") (pin "4") (pinfunction "GND_4") (pintype "bidirectional"))
      (node (ref "CON6") (pin "6") (pinfunction "GND_6") (pintype "bidirectional"))
      (node (ref "CON6") (pin "9") (pinfunction "GND_9") (pintype "bidirectional"))
      (node (ref "CON6") (pin "GND@1") (pinfunction "GND_GND@1") (pintype "power_in"))
      (node (ref "CON6") (pin "GND@2") (pinfunction "GND_GND@2") (pintype "power_in"))
      (node (ref "CON6") (pin "GND@3") (pinfunction "GND_GND@3") (pintype "power_in"))
      (node (ref "CON6") (pin "GND@4") (pinfunction "GND_GND@4") (pintype "power_in"))
      (node (ref "IC1") (pin "2") (pinfunction "GND_2") (pintype "bidirectional"))
      (node (ref "IC1") (pin "6") (pinfunction "PGND_6") (pintype "bidirectional"))
      (node (ref "IC2") (pin "2") (pinfunction "GND_2") (pintype "bidirectional"))
      (node (ref "IC2") (pin "6") (pinfunction "PGND_6") (pintype "bidirectional"))
      (node (ref "IC4") (pin "1") (pinfunction "A0_1") (pintype "input"))
      (node (ref "IC4") (pin "2") (pinfunction "A1_2") (pintype "input"))
      (node (ref "IC4") (pin "3") (pinfunction "A2_3") (pintype "input"))
      (node (ref "IC4") (pin "4") (pinfunction "GND_4") (pintype "power_in"))
      (node (ref "IC5") (pin "1") (pinfunction "DFO_1") (pintype "bidirectional"))
      (node (ref "IC5") (pin "19") (pinfunction "OGND_19") (pintype "power_in"))
      (node (ref "IC5") (pin "28") (pinfunction "OGND_28") (pintype "power_in"))
      (node (ref "IC5") (pin "3") (pinfunction "ST_3") (pintype "bidirectional"))
      (node (ref "IC5") (pin "39") (pinfunction "DGND_39") (pintype "power_in"))
      (node (ref "IC5") (pin "45") (pinfunction "OGND_45") (pintype "power_in"))
      (node (ref "IC5") (pin "5") (pinfunction "DGND_5") (pintype "power_in"))
      (node (ref "IC5") (pin "58") (pinfunction "OGND_58") (pintype "power_in"))
      (node (ref "IC5") (pin "68") (pinfunction "DGND_68") (pintype "power_in"))
      (node (ref "IC5") (pin "7") (pinfunction "~{STAG}_7") (pintype "bidirectional"))
      (node (ref "IC5") (pin "76") (pinfunction "OGND_76") (pintype "power_in"))
      (node (ref "IC5") (pin "79") (pinfunction "AGND_79") (pintype "power_in"))
      (node (ref "IC5") (pin "83") (pinfunction "AGND_83") (pintype "power_in"))
      (node (ref "IC5") (pin "87") (pinfunction "AGND_87") (pintype "power_in"))
      (node (ref "IC5") (pin "89") (pinfunction "AGND_89") (pintype "power_in"))
      (node (ref "IC5") (pin "92") (pinfunction "AGND_92") (pintype "power_in"))
      (node (ref "IC5") (pin "98") (pinfunction "PGND_98") (pintype "power_in"))
      (node (ref "IC6") (pin "21") (pinfunction "GND_21") (pintype "power_in"))
      (node (ref "IC6") (pin "3") (pinfunction "GND_3") (pintype "power_in"))
      (node (ref "IC6") (pin "5") (pinfunction "GND_5") (pintype "power_in"))
      (node (ref "IC7") (pin "18") (pinfunction "GND_18") (pintype "power_in"))
      (node (ref "IC7") (pin "21") (pinfunction "GND_21") (pintype "power_in"))
      (node (ref "IC7") (pin "25") (pinfunction "GND_25") (pintype "power_in"))
      (node (ref "IC7") (pin "26") (pinfunction "TEST_26") (pintype "input"))
      (node (ref "IC7") (pin "7") (pinfunction "GND_7") (pintype "power_in"))
      (node (ref "IC8") (pin "13") (pinfunction "GND_13") (pintype "power_in"))
      (node (ref "IC8") (pin "21") (pinfunction "GND_21") (pintype "power_in"))
      (node (ref "IC8") (pin "25") (pinfunction "D23_25") (pintype "bidirectional"))
      (node (ref "IC8") (pin "29") (pinfunction "GND_29") (pintype "power_in"))
      (node (ref "IC8") (pin "33") (pinfunction "GND_33") (pintype "power_in"))
      (node (ref "IC8") (pin "35") (pinfunction "GND_35") (pintype "power_in"))
      (node (ref "IC8") (pin "36") (pinfunction "GND_36") (pintype "power_in"))
      (node (ref "IC8") (pin "43") (pinfunction "GND_43") (pintype "power_in"))
      (node (ref "IC8") (pin "49") (pinfunction "GND_49") (pintype "power_in"))
      (node (ref "IC8") (pin "5") (pinfunction "GND_5") (pintype "power_in"))
      (node (ref "IC8") (pin "53") (pinfunction "GND_53") (pintype "power_in"))
      (node (ref "JP1") (pin "1") (pinfunction "1_1") (pintype "passive"))
      (node (ref "JP2") (pin "1") (pinfunction "1_1") (pintype "passive"))
      (node (ref "JP3") (pin "1") (pinfunction "1_1") (pintype "passive"))
      (node (ref "JP5") (pin "1") (pinfunction "1_1") (pintype "passive"))
      (node (ref "JP7") (pin "1") (pinfunction "1_1") (pintype "passive"))
      (node (ref "JP8") (pin "1") (pinfunction "1_1") (pintype "passive"))
      (node (ref "R1") (pin "1") (pinfunction "P$1_1") (pintype "passive"))
      (node (ref "R14") (pin "2") (pinfunction "P$2_2") (pintype "passive"))
      (node (ref "R19") (pin "3") (pinfunction "A_3") (pintype "passive"))
    )
    (net (code "21") (name "HDMI_CLK_N") (class "Default")
      (node (ref "CON2") (pin "12") (pinfunction "CLK-_12") (pintype "bidirectional"))
      (node (ref "IC5") (pin "94") (pinfunction "RXC-_94") (pintype "bidirectional"))
    )
    (net (code "22") (name "HDMI_CLK_P") (class "Default")
      (node (ref "CON2") (pin "10") (pinfunction "CLK+_10") (pintype "bidirectional"))
      (node (ref "IC5") (pin "93") (pinfunction "RXC+_93") (pintype "bidirectional"))
    )
    (net (code "23") (name "HDMI_DAT0_N") (class "Default")
      (node (ref "CON2") (pin "9") (pinfunction "DATA0-_9") (pintype "bidirectional"))
      (node (ref "IC5") (pin "91") (pinfunction "RX0-_91") (pintype "bidirectional"))
    )
    (net (code "24") (name "HDMI_DAT0_P") (class "Default")
      (node (ref "CON2") (pin "7") (pinfunction "DATA0+_7") (pintype "bidirectional"))
      (node (ref "IC5") (pin "90") (pinfunction "RX0+_90") (pintype "bidirectional"))
    )
    (net (code "25") (name "HDMI_DAT1_N") (class "Default")
      (node (ref "CON2") (pin "6") (pinfunction "DATA1-_6") (pintype "bidirectional"))
      (node (ref "IC5") (pin "86") (pinfunction "RX1-_86") (pintype "bidirectional"))
    )
    (net (code "26") (name "HDMI_DAT1_P") (class "Default")
      (node (ref "CON2") (pin "4") (pinfunction "DATA1+_4") (pintype "bidirectional"))
      (node (ref "IC5") (pin "85") (pinfunction "RX1+_85") (pintype "bidirectional"))
    )
    (net (code "27") (name "HDMI_DAT2_N") (class "Default")
      (node (ref "CON2") (pin "3") (pinfunction "DATA2-_3") (pintype "bidirectional"))
      (node (ref "IC5") (pin "81") (pinfunction "RX2-_81") (pintype "bidirectional"))
    )
    (net (code "28") (name "HDMI_DAT2_P") (class "Default")
      (node (ref "CON2") (pin "1") (pinfunction "DATA2+_1") (pintype "bidirectional"))
      (node (ref "IC5") (pin "80") (pinfunction "RX2+_80") (pintype "bidirectional"))
    )
    (net (code "29") (name "HDMI_OCK_INV") (class "Default")
      (node (ref "IC5") (pin "100") (pinfunction "OCK_INV_100") (pintype "bidirectional"))
      (node (ref "JP1") (pin "2") (pinfunction "2_2") (pintype "passive"))
      (node (ref "R6") (pin "1") (pinfunction "P$1_1") (pintype "passive"))
    )
    (net (code "30") (name "HDMI_PIXS") (class "Default")
      (node (ref "IC5") (pin "4") (pinfunction "PIXS_4") (pintype "bidirectional"))
      (node (ref "JP2") (pin "2") (pinfunction "2_2") (pintype "passive"))
      (node (ref "R5") (pin "1") (pinfunction "P$1_1") (pintype "passive"))
    )
    (net (code "31") (name "LVDS_0_N") (class "Default")
      (node (ref "CON6") (pin "7") (pinfunction "RA-_7") (pintype "bidirectional"))
      (node (ref "IC8") (pin "48") (pinfunction "Y0M_48") (pintype "bidirectional"))
    )
    (net (code "32") (name "LVDS_0_P") (class "Default")
      (node (ref "CON6") (pin "8") (pinfunction "RA+_8") (pintype "bidirectional"))
      (node (ref "IC8") (pin "47") (pinfunction "Y0P_47") (pintype "bidirectional"))
    )
    (net (code "33") (name "LVDS_1_N") (class "Default")
      (node (ref "CON6") (pin "10") (pinfunction "RB-_10") (pintype "bidirectional"))
      (node (ref "IC8") (pin "46") (pinfunction "Y1M_46") (pintype "bidirectional"))
    )
    (net (code "34") (name "LVDS_1_P") (class "Default")
      (node (ref "CON6") (pin "11") (pinfunction "RB+_11") (pintype "bidirectional"))
      (node (ref "IC8") (pin "45") (pinfunction "Y1P_45") (pintype "bidirectional"))
    )
    (net (code "35") (name "LVDS_2_N") (class "Default")
      (node (ref "CON6") (pin "13") (pinfunction "RC-_13") (pintype "bidirectional"))
      (node (ref "IC8") (pin "42") (pinfunction "Y2M_42") (pintype "bidirectional"))
    )
    (net (code "36") (name "LVDS_2_P") (class "Default")
      (node (ref "CON6") (pin "14") (pinfunction "RC+_14") (pintype "bidirectional"))
      (node (ref "IC8") (pin "41") (pinfunction "Y2P_41") (pintype "bidirectional"))
    )
    (net (code "37") (name "LVDS_3_N") (class "Default")
      (node (ref "CON6") (pin "19") (pinfunction "RDM-_19") (pintype "bidirectional"))
      (node (ref "IC8") (pin "38") (pinfunction "Y3M_38") (pintype "bidirectional"))
    )
    (net (code "38") (name "LVDS_3_P") (class "Default")
      (node (ref "CON6") (pin "20") (pinfunction "RDM+_20") (pintype "bidirectional"))
      (node (ref "IC8") (pin "37") (pinfunction "Y3P_37") (pintype "bidirectional"))
    )
    (net (code "39") (name "LVDS_CLK_N") (class "Default")
      (node (ref "CON6") (pin "16") (pinfunction "RCLK-_16") (pintype "bidirectional"))
      (node (ref "IC8") (pin "40") (pinfunction "CLKOUTM_40") (pintype "bidirectional"))
    )
    (net (code "40") (name "LVDS_CLK_P") (class "Default")
      (node (ref "CON6") (pin "17") (pinfunction "RCLK+_17") (pintype "bidirectional"))
      (node (ref "IC8") (pin "39") (pinfunction "CLKOUTP_39") (pintype "bidirectional"))
    )
    (net (code "41") (name "LVDS_LED_EN") (class "Default")
      (node (ref "CON6") (pin "25") (pinfunction "LED_EN_25") (pintype "bidirectional"))
      (node (ref "JP8") (pin "2") (pinfunction "2_2") (pintype "passive"))
      (node (ref "R4") (pin "1") (pinfunction "P$1_1") (pintype "passive"))
    )
    (net (code "42") (name "LVDS_PWM") (class "Default")
      (node (ref "CON6") (pin "24") (pinfunction "PWM_24") (pintype "bidirectional"))
      (node (ref "JP6") (pin "3") (pinfunction "3_3") (pintype "passive"))
    )
    (net (code "43") (name "LVDS_REVSCAN") (class "Default")
      (node (ref "CON6") (pin "5") (pinfunction "SHLI_5") (pintype "bidirectional"))
      (node (ref "JP7") (pin "2") (pinfunction "2_2") (pintype "passive"))
      (node (ref "R18") (pin "1") (pinfunction "P$1_1") (pintype "passive"))
    )
    (net (code "44") (name "Net-(C7-P$2)") (class "Default")
      (node (ref "C7") (pin "2") (pinfunction "P$2_2") (pintype "passive"))
      (node (ref "IC6") (pin "7") (pinfunction "PB6(PCINT6/XTAL1/TOSC1)_7") (pintype "bidirectional"))
      (node (ref "Q1") (pin "2") (pinfunction "2_2") (pintype "passive"))
    )
    (net (code "45") (name "Net-(C8-P$2)") (class "Default")
      (node (ref "C8") (pin "2") (pinfunction "P$2_2") (pintype "passive"))
      (node (ref "IC6") (pin "8") (pinfunction "PB7(PCINT7/XTAL2/TOSC2)_8") (pintype "bidirectional"))
      (node (ref "Q1") (pin "1") (pinfunction "1_1") (pintype "passive"))
    )
    (net (code "46") (name "Net-(C11-P$1)") (class "Default")
      (node (ref "C11") (pin "1") (pinfunction "P$1_1") (pintype "passive"))
      (node (ref "IC7") (pin "17") (pinfunction "3V3OUT_17") (pintype "output"))
    )
    (net (code "47") (name "Net-(CON1-1)") (class "Default")
      (node (ref "CON1") (pin "3") (pinfunction "1_3") (pintype "passive"))
      (node (ref "T1") (pin "2") (pinfunction "D_2") (pintype "passive"))
    )
    (net (code "48") (name "Net-(CON2-DETECT)") (class "Default")
      (node (ref "CON2") (pin "19") (pinfunction "DETECT_19") (pintype "bidirectional"))
      (node (ref "R7") (pin "1") (pinfunction "P$1_1") (pintype "passive"))
    )
    (net (code "49") (name "Net-(CON3-LED-A)") (class "Default")
      (node (ref "CON3") (pin "2") (pinfunction "LED-A_2") (pintype "bidirectional"))
      (node (ref "T2") (pin "2") (pinfunction "S_2") (pintype "passive"))
    )
    (net (code "50") (name "Net-(IC3-GND)") (class "Default")
      (node (ref "IC3") (pin "1") (pinfunction "GND_1") (pintype "input"))
      (node (ref "R13") (pin "1") (pinfunction "P$1_1") (pintype "passive"))
      (node (ref "R14") (pin "1") (pinfunction "P$1_1") (pintype "passive"))
    )
    (net (code "51") (name "Net-(IC5-DE)") (class "Default")
      (node (ref "IC5") (pin "46") (pinfunction "DE_46") (pintype "bidirectional"))
      (node (ref "R2") (pin "3M") (pinfunction "3M_3M") (pintype "bidirectional"))
    )
    (net (code "52") (name "Net-(IC5-HSYNC)") (class "Default")
      (node (ref "IC5") (pin "48") (pinfunction "HSYNC_48") (pintype "bidirectional"))
      (node (ref "R2") (pin "1M") (pinfunction "1M_1M") (pintype "bidirectional"))
    )
    (net (code "53") (name "Net-(IC5-ODCK)") (class "Default")
      (node (ref "IC5") (pin "44") (pinfunction "ODCK_44") (pintype "bidirectional"))
      (node (ref "R2") (pin "4M") (pinfunction "4M_4M") (pintype "bidirectional"))
    )
    (net (code "54") (name "Net-(IC5-QE0)") (class "Default")
      (node (ref "IC5") (pin "10") (pinfunction "QE0_10") (pintype "bidirectional"))
      (node (ref "R3") (pin "4M") (pinfunction "4M_4M") (pintype "bidirectional"))
    )
    (net (code "55") (name "Net-(IC5-QE1)") (class "Default")
      (node (ref "IC5") (pin "11") (pinfunction "QE1_11") (pintype "bidirectional"))
      (node (ref "R3") (pin "3M") (pinfunction "3M_3M") (pintype "bidirectional"))
    )
    (net (code "56") (name "Net-(IC5-QE2)") (class "Default")
      (node (ref "IC5") (pin "12") (pinfunction "QE2_12") (pintype "bidirectional"))
      (node (ref "R3") (pin "2M") (pinfunction "2M_2M") (pintype "bidirectional"))
    )
    (net (code "57") (name "Net-(IC5-QE3)") (class "Default")
      (node (ref "IC5") (pin "13") (pinfunction "QE3_13") (pintype "bidirectional"))
      (node (ref "R3") (pin "1M") (pinfunction "1M_1M") (pintype "bidirectional"))
    )
    (net (code "58") (name "Net-(IC5-QE4)") (class "Default")
      (node (ref "IC5") (pin "14") (pinfunction "QE4_14") (pintype "bidirectional"))
      (node (ref "R8") (pin "4M") (pinfunction "4M_4M") (pintype "bidirectional"))
    )
    (net (code "59") (name "Net-(IC5-QE5)") (class "Default")
      (node (ref "IC5") (pin "15") (pinfunction "QE5_15") (pintype "bidirectional"))
      (node (ref "R8") (pin "3M") (pinfunction "3M_3M") (pintype "bidirectional"))
    )
    (net (code "60") (name "Net-(IC5-QE6)") (class "Default")
      (node (ref "IC5") (pin "16") (pinfunction "QE6_16") (pintype "bidirectional"))
      (node (ref "R8") (pin "2M") (pinfunction "2M_2M") (pintype "bidirectional"))
    )
    (net (code "61") (name "Net-(IC5-QE7)") (class "Default")
      (node (ref "IC5") (pin "17") (pinfunction "QE7_17") (pintype "bidirectional"))
      (node (ref "R8") (pin "1M") (pinfunction "1M_1M") (pintype "bidirectional"))
    )
    (net (code "62") (name "Net-(IC5-QE8)") (class "Default")
      (node (ref "IC5") (pin "20") (pinfunction "QE8_20") (pintype "bidirectional"))
      (node (ref "R9") (pin "4M") (pinfunction "4M_4M") (pintype "bidirectional"))
    )
    (net (code "63") (name "Net-(IC5-QE9)") (class "Default")
      (node (ref "IC5") (pin "21") (pinfunction "QE9_21") (pintype "bidirectional"))
      (node (ref "R9") (pin "3M") (pinfunction "3M_3M") (pintype "bidirectional"))
    )
    (net (code "64") (name "Net-(IC5-QE10)") (class "Default")
      (node (ref "IC5") (pin "22") (pinfunction "QE10_22") (pintype "bidirectional"))
      (node (ref "R9") (pin "2M") (pinfunction "2M_2M") (pintype "bidirectional"))
    )
    (net (code "65") (name "Net-(IC5-QE11)") (class "Default")
      (node (ref "IC5") (pin "23") (pinfunction "QE11_23") (pintype "bidirectional"))
      (node (ref "R9") (pin "1M") (pinfunction "1M_1M") (pintype "bidirectional"))
    )
    (net (code "66") (name "Net-(IC5-QE12)") (class "Default")
      (node (ref "IC5") (pin "24") (pinfunction "QE12_24") (pintype "bidirectional"))
      (node (ref "R10") (pin "4M") (pinfunction "4M_4M") (pintype "bidirectional"))
    )
    (net (code "67") (name "Net-(IC5-QE13)") (class "Default")
      (node (ref "IC5") (pin "25") (pinfunction "QE13_25") (pintype "bidirectional"))
      (node (ref "R10") (pin "3M") (pinfunction "3M_3M") (pintype "bidirectional"))
    )
    (net (code "68") (name "Net-(IC5-QE14)") (class "Default")
      (node (ref "IC5") (pin "26") (pinfunction "QE14_26") (pintype "bidirectional"))
      (node (ref "R10") (pin "2M") (pinfunction "2M_2M") (pintype "bidirectional"))
    )
    (net (code "69") (name "Net-(IC5-QE15)") (class "Default")
      (node (ref "IC5") (pin "27") (pinfunction "QE15_27") (pintype "bidirectional"))
      (node (ref "R10") (pin "1M") (pinfunction "1M_1M") (pintype "bidirectional"))
    )
    (net (code "70") (name "Net-(IC5-QE16)") (class "Default")
      (node (ref "IC5") (pin "30") (pinfunction "QE16_30") (pintype "bidirectional"))
      (node (ref "R11") (pin "4M") (pinfunction "4M_4M") (pintype "bidirectional"))
    )
    (net (code "71") (name "Net-(IC5-QE17)") (class "Default")
      (node (ref "IC5") (pin "31") (pinfunction "QE17_31") (pintype "bidirectional"))
      (node (ref "R11") (pin "3M") (pinfunction "3M_3M") (pintype "bidirectional"))
    )
    (net (code "72") (name "Net-(IC5-QE18)") (class "Default")
      (node (ref "IC5") (pin "32") (pinfunction "QE18_32") (pintype "bidirectional"))
      (node (ref "R11") (pin "2M") (pinfunction "2M_2M") (pintype "bidirectional"))
    )
    (net (code "73") (name "Net-(IC5-QE19)") (class "Default")
      (node (ref "IC5") (pin "33") (pinfunction "QE19_33") (pintype "bidirectional"))
      (node (ref "R11") (pin "1M") (pinfunction "1M_1M") (pintype "bidirectional"))
    )
    (net (code "74") (name "Net-(IC5-QE20)") (class "Default")
      (node (ref "IC5") (pin "34") (pinfunction "QE20_34") (pintype "bidirectional"))
      (node (ref "R12") (pin "4M") (pinfunction "4M_4M") (pintype "bidirectional"))
    )
    (net (code "75") (name "Net-(IC5-QE21)") (class "Default")
      (node (ref "IC5") (pin "35") (pinfunction "QE21_35") (pintype "bidirectional"))
      (node (ref "R12") (pin "3M") (pinfunction "3M_3M") (pintype "bidirectional"))
    )
    (net (code "76") (name "Net-(IC5-QE22)") (class "Default")
      (node (ref "IC5") (pin "36") (pinfunction "QE22_36") (pintype "bidirectional"))
      (node (ref "R12") (pin "2M") (pinfunction "2M_2M") (pintype "bidirectional"))
    )
    (net (code "77") (name "Net-(IC5-QE23)") (class "Default")
      (node (ref "IC5") (pin "37") (pinfunction "QE23_37") (pintype "bidirectional"))
      (node (ref "R12") (pin "1M") (pinfunction "1M_1M") (pintype "bidirectional"))
    )
    (net (code "78") (name "Net-(IC5-VSYNC)") (class "Default")
      (node (ref "IC5") (pin "47") (pinfunction "VSYNC_47") (pintype "bidirectional"))
      (node (ref "R2") (pin "2M") (pinfunction "2M_2M") (pintype "bidirectional"))
    )
    (net (code "79") (name "Net-(IC7-USBDM)") (class "Default")
      (node (ref "IC7") (pin "16") (pinfunction "USBDM_16") (pintype "bidirectional"))
      (node (ref "R23") (pin "2") (pinfunction "P$2_2") (pintype "passive"))
    )
    (net (code "80") (name "Net-(IC7-USBDP)") (class "Default")
      (node (ref "IC7") (pin "15") (pinfunction "USBDP_15") (pintype "bidirectional"))
      (node (ref "R22") (pin "2") (pinfunction "P$2_2") (pintype "passive"))
    )
    (net (code "81") (name "Net-(R1-P$2)") (class "Default")
      (node (ref "D1") (pin "A") (pinfunction "A_A") (pintype "passive"))
      (node (ref "R1") (pin "2") (pinfunction "P$2_2") (pintype "passive"))
      (node (ref "T1") (pin "1") (pinfunction "G_1") (pintype "passive"))
    )
    (net (code "82") (name "Net-(R20-P$1)") (class "Default")
      (node (ref "R20") (pin "1") (pinfunction "P$1_1") (pintype "passive"))
      (node (ref "R21") (pin "1") (pinfunction "P$1_1") (pintype "passive"))
      (node (ref "T2") (pin "3") (pinfunction "D_3") (pintype "passive"))
    )
    (net (code "83") (name "RGB_DE") (class "Default")
      (node (ref "CON3") (pin "34") (pinfunction "DEN_34") (pintype "bidirectional"))
      (node (ref "IC8") (pin "30") (pinfunction "D26_30") (pintype "bidirectional"))
      (node (ref "R2") (pin "3P") (pinfunction "3P_3P") (pintype "bidirectional"))
    )
    (net (code "84") (name "RGB_DISP") (class "Default")
      (node (ref "CON3") (pin "31") (pinfunction "DISP_31") (pintype "bidirectional"))
      (node (ref "JP3") (pin "2") (pinfunction "2_2") (pintype "passive"))
      (node (ref "R15") (pin "1") (pinfunction "P$1_1") (pintype "passive"))
    )
    (net (code "85") (name "RGB_EVEN_B0") (class "Default")
      (node (ref "CON3") (pin "21") (pinfunction "B0_21") (pintype "bidirectional"))
      (node (ref "IC8") (pin "15") (pinfunction "D15_15") (pintype "bidirectional"))
      (node (ref "R3") (pin "4P") (pinfunction "4P_4P") (pintype "bidirectional"))
    )
    (net (code "86") (name "RGB_EVEN_B1") (class "Default")
      (node (ref "CON3") (pin "22") (pinfunction "B1_22") (pintype "bidirectional"))
      (node (ref "IC8") (pin "19") (pinfunction "D18_19") (pintype "bidirectional"))
      (node (ref "R3") (pin "3P") (pinfunction "3P_3P") (pintype "bidirectional"))
    )
    (net (code "87") (name "RGB_EVEN_B2") (class "Default")
      (node (ref "CON3") (pin "23") (pinfunction "B2_23") (pintype "bidirectional"))
      (node (ref "IC8") (pin "20") (pinfunction "D19_20") (pintype "bidirectional"))
      (node (ref "R3") (pin "2P") (pinfunction "2P_2P") (pintype "bidirectional"))
    )
    (net (code "88") (name "RGB_EVEN_B3") (class "Default")
      (node (ref "CON3") (pin "24") (pinfunction "B3_24") (pintype "bidirectional"))
      (node (ref "IC8") (pin "22") (pinfunction "D20_22") (pintype "bidirectional"))
      (node (ref "R3") (pin "1P") (pinfunction "1P_1P") (pintype "bidirectional"))
    )
    (net (code "89") (name "RGB_EVEN_B4") (class "Default")
      (node (ref "CON3") (pin "25") (pinfunction "B4_25") (pintype "bidirectional"))
      (node (ref "IC8") (pin "23") (pinfunction "D21_23") (pintype "bidirectional"))
      (node (ref "R8") (pin "4P") (pinfunction "4P_4P") (pintype "bidirectional"))
    )
    (net (code "90") (name "RGB_EVEN_B5") (class "Default")
      (node (ref "CON3") (pin "26") (pinfunction "B5_26") (pintype "bidirectional"))
      (node (ref "IC8") (pin "24") (pinfunction "D22_24") (pintype "bidirectional"))
      (node (ref "R8") (pin "3P") (pinfunction "3P_3P") (pintype "bidirectional"))
    )
    (net (code "91") (name "RGB_EVEN_B6") (class "Default")
      (node (ref "CON3") (pin "27") (pinfunction "B6_27") (pintype "bidirectional"))
      (node (ref "IC8") (pin "16") (pinfunction "D16_16") (pintype "bidirectional"))
      (node (ref "R8") (pin "2P") (pinfunction "2P_2P") (pintype "bidirectional"))
    )
    (net (code "92") (name "RGB_EVEN_B7") (class "Default")
      (node (ref "CON3") (pin "28") (pinfunction "B7_28") (pintype "bidirectional"))
      (node (ref "IC8") (pin "18") (pinfunction "D17_18") (pintype "bidirectional"))
      (node (ref "R8") (pin "1P") (pinfunction "1P_1P") (pintype "bidirectional"))
    )
    (net (code "93") (name "RGB_EVEN_G0") (class "Default")
      (node (ref "CON3") (pin "13") (pinfunction "G0_13") (pintype "bidirectional"))
      (node (ref "IC8") (pin "4") (pinfunction "D7_4") (pintype "bidirectional"))
      (node (ref "R9") (pin "4P") (pinfunction "4P_4P") (pintype "bidirectional"))
    )
    (net (code "94") (name "RGB_EVEN_G1") (class "Default")
      (node (ref "CON3") (pin "14") (pinfunction "G1_14") (pintype "bidirectional"))
      (node (ref "IC8") (pin "6") (pinfunction "D8_6") (pintype "bidirectional"))
      (node (ref "R9") (pin "3P") (pinfunction "3P_3P") (pintype "bidirectional"))
    )
    (net (code "95") (name "RGB_EVEN_G2") (class "Default")
      (node (ref "CON3") (pin "15") (pinfunction "G2_15") (pintype "bidirectional"))
      (node (ref "IC8") (pin "7") (pinfunction "D9_7") (pintype "bidirectional"))
      (node (ref "R9") (pin "2P") (pinfunction "2P_2P") (pintype "bidirectional"))
    )
    (net (code "96") (name "RGB_EVEN_G3") (class "Default")
      (node (ref "CON3") (pin "16") (pinfunction "G3_16") (pintype "bidirectional"))
      (node (ref "IC8") (pin "11") (pinfunction "D12_11") (pintype "bidirectional"))
      (node (ref "R9") (pin "1P") (pinfunction "1P_1P") (pintype "bidirectional"))
    )
    (net (code "97") (name "RGB_EVEN_G4") (class "Default")
      (node (ref "CON3") (pin "17") (pinfunction "G4_17") (pintype "bidirectional"))
      (node (ref "IC8") (pin "12") (pinfunction "D13_12") (pintype "bidirectional"))
      (node (ref "R10") (pin "4P") (pinfunction "4P_4P") (pintype "bidirectional"))
    )
    (net (code "98") (name "RGB_EVEN_G5") (class "Default")
      (node (ref "CON3") (pin "18") (pinfunction "G5_18") (pintype "bidirectional"))
      (node (ref "IC8") (pin "14") (pinfunction "D14_14") (pintype "bidirectional"))
      (node (ref "R10") (pin "3P") (pinfunction "3P_3P") (pintype "bidirectional"))
    )
    (net (code "99") (name "RGB_EVEN_G6") (class "Default")
      (node (ref "CON3") (pin "19") (pinfunction "G6_19") (pintype "bidirectional"))
      (node (ref "IC8") (pin "8") (pinfunction "D10_8") (pintype "bidirectional"))
      (node (ref "R10") (pin "2P") (pinfunction "2P_2P") (pintype "bidirectional"))
    )
    (net (code "100") (name "RGB_EVEN_G7") (class "Default")
      (node (ref "CON3") (pin "20") (pinfunction "G7_20") (pintype "bidirectional"))
      (node (ref "IC8") (pin "10") (pinfunction "D11_10") (pintype "bidirectional"))
      (node (ref "R10") (pin "1P") (pinfunction "1P_1P") (pintype "bidirectional"))
    )
    (net (code "101") (name "RGB_EVEN_R0") (class "Default")
      (node (ref "CON3") (pin "5") (pinfunction "R0_5") (pintype "bidirectional"))
      (node (ref "IC8") (pin "51") (pinfunction "D0_51") (pintype "bidirectional"))
      (node (ref "R11") (pin "4P") (pinfunction "4P_4P") (pintype "bidirectional"))
    )
    (net (code "102") (name "RGB_EVEN_R1") (class "Default")
      (node (ref "CON3") (pin "6") (pinfunction "R1_6") (pintype "bidirectional"))
      (node (ref "IC8") (pin "52") (pinfunction "D1_52") (pintype "bidirectional"))
      (node (ref "R11") (pin "3P") (pinfunction "3P_3P") (pintype "bidirectional"))
    )
    (net (code "103") (name "RGB_EVEN_R2") (class "Default")
      (node (ref "CON3") (pin "7") (pinfunction "R2_7") (pintype "bidirectional"))
      (node (ref "IC8") (pin "54") (pinfunction "D2_54") (pintype "bidirectional"))
      (node (ref "R11") (pin "2P") (pinfunction "2P_2P") (pintype "bidirectional"))
    )
    (net (code "104") (name "RGB_EVEN_R3") (class "Default")
      (node (ref "CON3") (pin "8") (pinfunction "R3_8") (pintype "bidirectional"))
      (node (ref "IC8") (pin "55") (pinfunction "D3_55") (pintype "bidirectional"))
      (node (ref "R11") (pin "1P") (pinfunction "1P_1P") (pintype "bidirectional"))
    )
    (net (code "105") (name "RGB_EVEN_R4") (class "Default")
      (node (ref "CON3") (pin "9") (pinfunction "R4_9") (pintype "bidirectional"))
      (node (ref "IC8") (pin "56") (pinfunction "D4_56") (pintype "bidirectional"))
      (node (ref "R12") (pin "4P") (pinfunction "4P_4P") (pintype "bidirectional"))
    )
    (net (code "106") (name "RGB_EVEN_R5") (class "Default")
      (node (ref "CON3") (pin "10") (pinfunction "R5_10") (pintype "bidirectional"))
      (node (ref "IC8") (pin "3") (pinfunction "D6_3") (pintype "bidirectional"))
      (node (ref "R12") (pin "3P") (pinfunction "3P_3P") (pintype "bidirectional"))
    )
    (net (code "107") (name "RGB_EVEN_R6") (class "Default")
      (node (ref "CON3") (pin "11") (pinfunction "R6_11") (pintype "bidirectional"))
      (node (ref "IC8") (pin "50") (pinfunction "D27_50") (pintype "bidirectional"))
      (node (ref "R12") (pin "2P") (pinfunction "2P_2P") (pintype "bidirectional"))
    )
    (net (code "108") (name "RGB_EVEN_R7") (class "Default")
      (node (ref "CON3") (pin "12") (pinfunction "R7_12") (pintype "bidirectional"))
      (node (ref "IC8") (pin "2") (pinfunction "D5_2") (pintype "bidirectional"))
      (node (ref "R12") (pin "1P") (pinfunction "1P_1P") (pintype "bidirectional"))
    )
    (net (code "109") (name "RGB_HSYNC") (class "Default")
      (node (ref "CON3") (pin "32") (pinfunction "HSYNC_32") (pintype "bidirectional"))
      (node (ref "IC8") (pin "27") (pinfunction "D24_27") (pintype "bidirectional"))
      (node (ref "R2") (pin "2P") (pinfunction "2P_2P") (pintype "bidirectional"))
    )
    (net (code "110") (name "RGB_ODCK") (class "Default")
      (node (ref "CON3") (pin "30") (pinfunction "CLK_30") (pintype "bidirectional"))
      (node (ref "R2") (pin "4P") (pinfunction "4P_4P") (pintype "bidirectional"))
    )
    (net (code "111") (name "RGB_PWM") (class "Default")
      (node (ref "JP4") (pin "3") (pinfunction "3_3") (pintype "passive"))
      (node (ref "JP6") (pin "1") (pinfunction "1_1") (pintype "passive"))
    )
    (net (code "112") (name "RGB_PWM_EN") (class "Default")
      (node (ref "JP4") (pin "2") (pinfunction "2_2") (pintype "passive"))
      (node (ref "T2") (pin "1") (pinfunction "G_1") (pintype "passive"))
    )
    (net (code "113") (name "RGB_VSYNC") (class "Default")
      (node (ref "CON3") (pin "33") (pinfunction "VSYNC_33") (pintype "bidirectional"))
      (node (ref "IC8") (pin "28") (pinfunction "D25_28") (pintype "bidirectional"))
      (node (ref "R2") (pin "1P") (pinfunction "1P_1P") (pintype "bidirectional"))
    )
    (net (code "114") (name "USB_D+") (class "Default")
      (node (ref "CON4") (pin "3") (pinfunction "D+_3") (pintype "bidirectional"))
      (node (ref "R23") (pin "1") (pinfunction "P$1_1") (pintype "passive"))
    )
    (net (code "115") (name "USB_D-") (class "Default")
      (node (ref "CON4") (pin "2") (pinfunction "D-_2") (pintype "bidirectional"))
      (node (ref "R22") (pin "1") (pinfunction "P$1_1") (pintype "passive"))
    )
    (net (code "116") (name "unconnected-(CON2-CEC-Pad13)") (class "Default")
      (node (ref "CON2") (pin "13") (pinfunction "CEC_13") (pintype "bidirectional"))
    )
    (net (code "117") (name "unconnected-(CON2-NC-Pad14)") (class "Default")
      (node (ref "CON2") (pin "14") (pinfunction "NC_14") (pintype "bidirectional"))
    )
    (net (code "118") (name "unconnected-(CON3-NC-Pad35)") (class "Default")
      (node (ref "CON3") (pin "35") (pinfunction "NC_35") (pintype "bidirectional"))
    )
    (net (code "119") (name "unconnected-(CON3-XL-Pad39)") (class "Default")
      (node (ref "CON3") (pin "39") (pinfunction "XL_39") (pintype "bidirectional"))
    )
    (net (code "120") (name "unconnected-(CON3-XR-Pad37)") (class "Default")
      (node (ref "CON3") (pin "37") (pinfunction "XR_37") (pintype "bidirectional"))
    )
    (net (code "121") (name "unconnected-(CON3-YD-Pad38)") (class "Default")
      (node (ref "CON3") (pin "38") (pinfunction "YD_38") (pintype "bidirectional"))
    )
    (net (code "122") (name "unconnected-(CON3-YU-Pad40)") (class "Default")
      (node (ref "CON3") (pin "40") (pinfunction "YU_40") (pintype "bidirectional"))
    )
    (net (code "123") (name "unconnected-(CON4-ID-Pad4)") (class "Default")
      (node (ref "CON4") (pin "4") (pinfunction "ID_4") (pintype "bidirectional"))
    )
    (net (code "124") (name "unconnected-(CON6-NC-Pad27)") (class "Default")
      (node (ref "CON6") (pin "27") (pinfunction "NC_27") (pintype "bidirectional"))
    )
    (net (code "125") (name "unconnected-(CON6-TP-Pad22)") (class "Default")
      (node (ref "CON6") (pin "22") (pinfunction "TP_22") (pintype "bidirectional"))
    )
    (net (code "126") (name "unconnected-(CON6-TP-Pad23)") (class "Default")
      (node (ref "CON6") (pin "23") (pinfunction "TP_23") (pintype "bidirectional"))
    )
    (net (code "127") (name "unconnected-(IC1-EN-Pad5)") (class "Default")
      (node (ref "IC1") (pin "5") (pinfunction "EN_5") (pintype "bidirectional"))
    )
    (net (code "128") (name "unconnected-(IC1-PG-Pad4)") (class "Default")
      (node (ref "IC1") (pin "4") (pinfunction "PG_4") (pintype "bidirectional"))
    )
    (net (code "129") (name "unconnected-(IC2-EN-Pad5)") (class "Default")
      (node (ref "IC2") (pin "5") (pinfunction "EN_5") (pintype "bidirectional"))
    )
    (net (code "130") (name "unconnected-(IC2-PG-Pad4)") (class "Default")
      (node (ref "IC2") (pin "4") (pinfunction "PG_4") (pintype "bidirectional"))
    )
    (net (code "131") (name "unconnected-(IC5-CTL1-Pad40)") (class "Default")
      (node (ref "IC5") (pin "40") (pinfunction "CTL1_40") (pintype "bidirectional"))
    )
    (net (code "132") (name "unconnected-(IC5-CTL2-Pad41)") (class "Default")
      (node (ref "IC5") (pin "41") (pinfunction "CTL2_41") (pintype "bidirectional"))
    )
    (net (code "133") (name "unconnected-(IC5-CTL3-Pad42)") (class "Default")
      (node (ref "IC5") (pin "42") (pinfunction "CTL3_42") (pintype "bidirectional"))
    )
    (net (code "134") (name "unconnected-(IC5-EXT_RES-Pad96)") (class "Default")
      (node (ref "IC5") (pin "96") (pinfunction "EXT_RES_96") (pintype "bidirectional"))
    )
    (net (code "135") (name "unconnected-(IC5-QO0-Pad49)") (class "Default")
      (node (ref "IC5") (pin "49") (pinfunction "QO0_49") (pintype "bidirectional"))
    )
    (net (code "136") (name "unconnected-(IC5-QO1-Pad50)") (class "Default")
      (node (ref "IC5") (pin "50") (pinfunction "QO1_50") (pintype "bidirectional"))
    )
    (net (code "137") (name "unconnected-(IC5-QO2-Pad51)") (class "Default")
      (node (ref "IC5") (pin "51") (pinfunction "QO2_51") (pintype "bidirectional"))
    )
    (net (code "138") (name "unconnected-(IC5-QO3-Pad52)") (class "Default")
      (node (ref "IC5") (pin "52") (pinfunction "QO3_52") (pintype "bidirectional"))
    )
    (net (code "139") (name "unconnected-(IC5-QO4-Pad53)") (class "Default")
      (node (ref "IC5") (pin "53") (pinfunction "QO4_53") (pintype "bidirectional"))
    )
    (net (code "140") (name "unconnected-(IC5-QO5-Pad54)") (class "Default")
      (node (ref "IC5") (pin "54") (pinfunction "QO5_54") (pintype "bidirectional"))
    )
    (net (code "141") (name "unconnected-(IC5-QO6-Pad55)") (class "Default")
      (node (ref "IC5") (pin "55") (pinfunction "QO6_55") (pintype "bidirectional"))
    )
    (net (code "142") (name "unconnected-(IC5-QO7-Pad56)") (class "Default")
      (node (ref "IC5") (pin "56") (pinfunction "QO7_56") (pintype "bidirectional"))
    )
    (net (code "143") (name "unconnected-(IC5-QO8-Pad59)") (class "Default")
      (node (ref "IC5") (pin "59") (pinfunction "QO8_59") (pintype "bidirectional"))
    )
    (net (code "144") (name "unconnected-(IC5-QO9-Pad60)") (class "Default")
      (node (ref "IC5") (pin "60") (pinfunction "QO9_60") (pintype "bidirectional"))
    )
    (net (code "145") (name "unconnected-(IC5-QO10-Pad61)") (class "Default")
      (node (ref "IC5") (pin "61") (pinfunction "QO10_61") (pintype "bidirectional"))
    )
    (net (code "146") (name "unconnected-(IC5-QO11-Pad62)") (class "Default")
      (node (ref "IC5") (pin "62") (pinfunction "QO11_62") (pintype "bidirectional"))
    )
    (net (code "147") (name "unconnected-(IC5-QO12-Pad63)") (class "Default")
      (node (ref "IC5") (pin "63") (pinfunction "QO12_63") (pintype "bidirectional"))
    )
    (net (code "148") (name "unconnected-(IC5-QO13-Pad64)") (class "Default")
      (node (ref "IC5") (pin "64") (pinfunction "QO13_64") (pintype "bidirectional"))
    )
    (net (code "149") (name "unconnected-(IC5-QO14-Pad65)") (class "Default")
      (node (ref "IC5") (pin "65") (pinfunction "QO14_65") (pintype "bidirectional"))
    )
    (net (code "150") (name "unconnected-(IC5-QO15-Pad66)") (class "Default")
      (node (ref "IC5") (pin "66") (pinfunction "QO15_66") (pintype "bidirectional"))
    )
    (net (code "151") (name "unconnected-(IC5-QO16-Pad69)") (class "Default")
      (node (ref "IC5") (pin "69") (pinfunction "QO16_69") (pintype "bidirectional"))
    )
    (net (code "152") (name "unconnected-(IC5-QO17-Pad70)") (class "Default")
      (node (ref "IC5") (pin "70") (pinfunction "QO17_70") (pintype "bidirectional"))
    )
    (net (code "153") (name "unconnected-(IC5-QO18-Pad71)") (class "Default")
      (node (ref "IC5") (pin "71") (pinfunction "QO18_71") (pintype "bidirectional"))
    )
    (net (code "154") (name "unconnected-(IC5-QO19-Pad72)") (class "Default")
      (node (ref "IC5") (pin "72") (pinfunction "QO19_72") (pintype "bidirectional"))
    )
    (net (code "155") (name "unconnected-(IC5-QO20-Pad73)") (class "Default")
      (node (ref "IC5") (pin "73") (pinfunction "QO20_73") (pintype "bidirectional"))
    )
    (net (code "156") (name "unconnected-(IC5-QO21-Pad74)") (class "Default")
      (node (ref "IC5") (pin "74") (pinfunction "QO21_74") (pintype "bidirectional"))
    )
    (net (code "157") (name "unconnected-(IC5-QO22-Pad75)") (class "Default")
      (node (ref "IC5") (pin "75") (pinfunction "QO22_75") (pintype "bidirectional"))
    )
    (net (code "158") (name "unconnected-(IC5-QO23-Pad77)") (class "Default")
      (node (ref "IC5") (pin "77") (pinfunction "QO23_77") (pintype "bidirectional"))
    )
    (net (code "159") (name "unconnected-(IC5-SCDT-Pad8)") (class "Default")
      (node (ref "IC5") (pin "8") (pinfunction "SCDT_8") (pintype "bidirectional"))
    )
    (net (code "160") (name "unconnected-(IC5-~{PDO}-Pad9)") (class "Default")
      (node (ref "IC5") (pin "9") (pinfunction "~{PDO}_9") (pintype "bidirectional"))
    )
    (net (code "161") (name "unconnected-(IC5-~{PD}-Pad2)") (class "Default")
      (node (ref "IC5") (pin "2") (pinfunction "~{PD}_2") (pintype "bidirectional"))
    )
    (net (code "162") (name "unconnected-(IC6-(PCINT18{slash}INT0)PD2-Pad32)") (class "Default")
      (node (ref "IC6") (pin "32") (pinfunction "(PCINT18/INT0)PD2_32") (pintype "bidirectional"))
    )
    (net (code "163") (name "unconnected-(IC6-(PCINT19{slash}OC2B{slash}INT1)PD3-Pad1)") (class "Default")
      (node (ref "IC6") (pin "1") (pinfunction "(PCINT19/OC2B/INT1)PD3_1") (pintype "bidirectional"))
    )
    (net (code "164") (name "unconnected-(IC6-(PCINT20{slash}XCK{slash}T0)PD4-Pad2)") (class "Default")
      (node (ref "IC6") (pin "2") (pinfunction "(PCINT20/XCK/T0)PD4_2") (pintype "bidirectional"))
    )
    (net (code "165") (name "unconnected-(IC6-(PCINT21{slash}OC0B{slash}T1)PD5-Pad9)") (class "Default")
      (node (ref "IC6") (pin "9") (pinfunction "(PCINT21/OC0B/T1)PD5_9") (pintype "bidirectional"))
    )
    (net (code "166") (name "unconnected-(IC6-(PCINT22{slash}OC0A{slash}AIN0)PD6-Pad10)") (class "Default")
      (node (ref "IC6") (pin "10") (pinfunction "(PCINT22/OC0A/AIN0)PD6_10") (pintype "bidirectional"))
    )
    (net (code "167") (name "unconnected-(IC6-(PCINT23{slash}AIN1)PD7-Pad11)") (class "Default")
      (node (ref "IC6") (pin "11") (pinfunction "(PCINT23/AIN1)PD7_11") (pintype "bidirectional"))
    )
    (net (code "168") (name "unconnected-(IC6-ADC6-Pad19)") (class "Default")
      (node (ref "IC6") (pin "19") (pinfunction "ADC6_19") (pintype "bidirectional"))
    )
    (net (code "169") (name "unconnected-(IC6-ADC7-Pad22)") (class "Default")
      (node (ref "IC6") (pin "22") (pinfunction "ADC7_22") (pintype "bidirectional"))
    )
    (net (code "170") (name "unconnected-(IC6-PB0(PCINT0{slash}CLKO{slash}ICP1)-Pad12)") (class "Default")
      (node (ref "IC6") (pin "12") (pinfunction "PB0(PCINT0/CLKO/ICP1)_12") (pintype "bidirectional"))
    )
    (net (code "171") (name "unconnected-(IC6-PB2(SS{slash}OC1B{slash}PCINT2)-Pad14)") (class "Default")
      (node (ref "IC6") (pin "14") (pinfunction "PB2(SS/OC1B/PCINT2)_14") (pintype "bidirectional"))
    )
    (net (code "172") (name "unconnected-(IC6-PC1(ADC1{slash}PCINT9)-Pad24)") (class "Default")
      (node (ref "IC6") (pin "24") (pinfunction "PC1(ADC1/PCINT9)_24") (pintype "bidirectional"))
    )
    (net (code "173") (name "unconnected-(IC6-PC2(ADC2{slash}PCINT10)-Pad25)") (class "Default")
      (node (ref "IC6") (pin "25") (pinfunction "PC2(ADC2/PCINT10)_25") (pintype "bidirectional"))
    )
    (net (code "174") (name "unconnected-(IC6-PC3(ADC3{slash}PCINT11)-Pad26)") (class "Default")
      (node (ref "IC6") (pin "26") (pinfunction "PC3(ADC3/PCINT11)_26") (pintype "bidirectional"))
    )
    (net (code "175") (name "unconnected-(IC7-CBUS0-Pad23)") (class "Default")
      (node (ref "IC7") (pin "23") (pinfunction "CBUS0_23") (pintype "bidirectional"))
    )
    (net (code "176") (name "unconnected-(IC7-CBUS1-Pad22)") (class "Default")
      (node (ref "IC7") (pin "22") (pinfunction "CBUS1_22") (pintype "bidirectional"))
    )
    (net (code "177") (name "unconnected-(IC7-CBUS2-Pad13)") (class "Default")
      (node (ref "IC7") (pin "13") (pinfunction "CBUS2_13") (pintype "bidirectional"))
    )
    (net (code "178") (name "unconnected-(IC7-CBUS3-Pad14)") (class "Default")
      (node (ref "IC7") (pin "14") (pinfunction "CBUS3_14") (pintype "bidirectional"))
    )
    (net (code "179") (name "unconnected-(IC7-CBUS4-Pad12)") (class "Default")
      (node (ref "IC7") (pin "12") (pinfunction "CBUS4_12") (pintype "bidirectional"))
    )
    (net (code "180") (name "unconnected-(IC7-OSCI-Pad27)") (class "Default")
      (node (ref "IC7") (pin "27") (pinfunction "OSCI_27") (pintype "input"))
    )
    (net (code "181") (name "unconnected-(IC7-OSCO-Pad28)") (class "Default")
      (node (ref "IC7") (pin "28") (pinfunction "OSCO_28") (pintype "output"))
    )
    (net (code "182") (name "unconnected-(IC7-~{CTS}-Pad11)") (class "Default")
      (node (ref "IC7") (pin "11") (pinfunction "~{CTS}_11") (pintype "input"))
    )
    (net (code "183") (name "unconnected-(IC7-~{DCD}-Pad10)") (class "Default")
      (node (ref "IC7") (pin "10") (pinfunction "~{DCD}_10") (pintype "input"))
    )
    (net (code "184") (name "unconnected-(IC7-~{DSR}-Pad9)") (class "Default")
      (node (ref "IC7") (pin "9") (pinfunction "~{DSR}_9") (pintype "input"))
    )
    (net (code "185") (name "unconnected-(IC7-~{DTR}-Pad2)") (class "Default")
      (node (ref "IC7") (pin "2") (pinfunction "~{DTR}_2") (pintype "output"))
    )
    (net (code "186") (name "unconnected-(IC7-~{RI}-Pad6)") (class "Default")
      (node (ref "IC7") (pin "6") (pinfunction "~{RI}_6") (pintype "input"))
    )
    (net (code "187") (name "unconnected-(IC7-~{RTS}-Pad3)") (class "Default")
      (node (ref "IC7") (pin "3") (pinfunction "~{RTS}_3") (pintype "output"))
    )
    (net (code "188") (name "unconnected-(IC8-CLKIN-Pad31)") (class "Default")
      (node (ref "IC8") (pin "31") (pinfunction "CLKIN_31") (pintype "bidirectional"))
    )
    (net (code "189") (name "unconnected-(IC8-CLKSEL-Pad17)") (class "Default")
      (node (ref "IC8") (pin "17") (pinfunction "CLKSEL_17") (pintype "bidirectional"))
    )
    (net (code "190") (name "unconnected-(IC8-~{SHTDN}-Pad32)") (class "Default")
      (node (ref "IC8") (pin "32") (pinfunction "~{SHTDN}_32") (pintype "bidirectional"))
    )
  )
)
